# 2VFAT_OH2_OCT1.net
KiCad netlist of a schematic drawn in Altium Designer
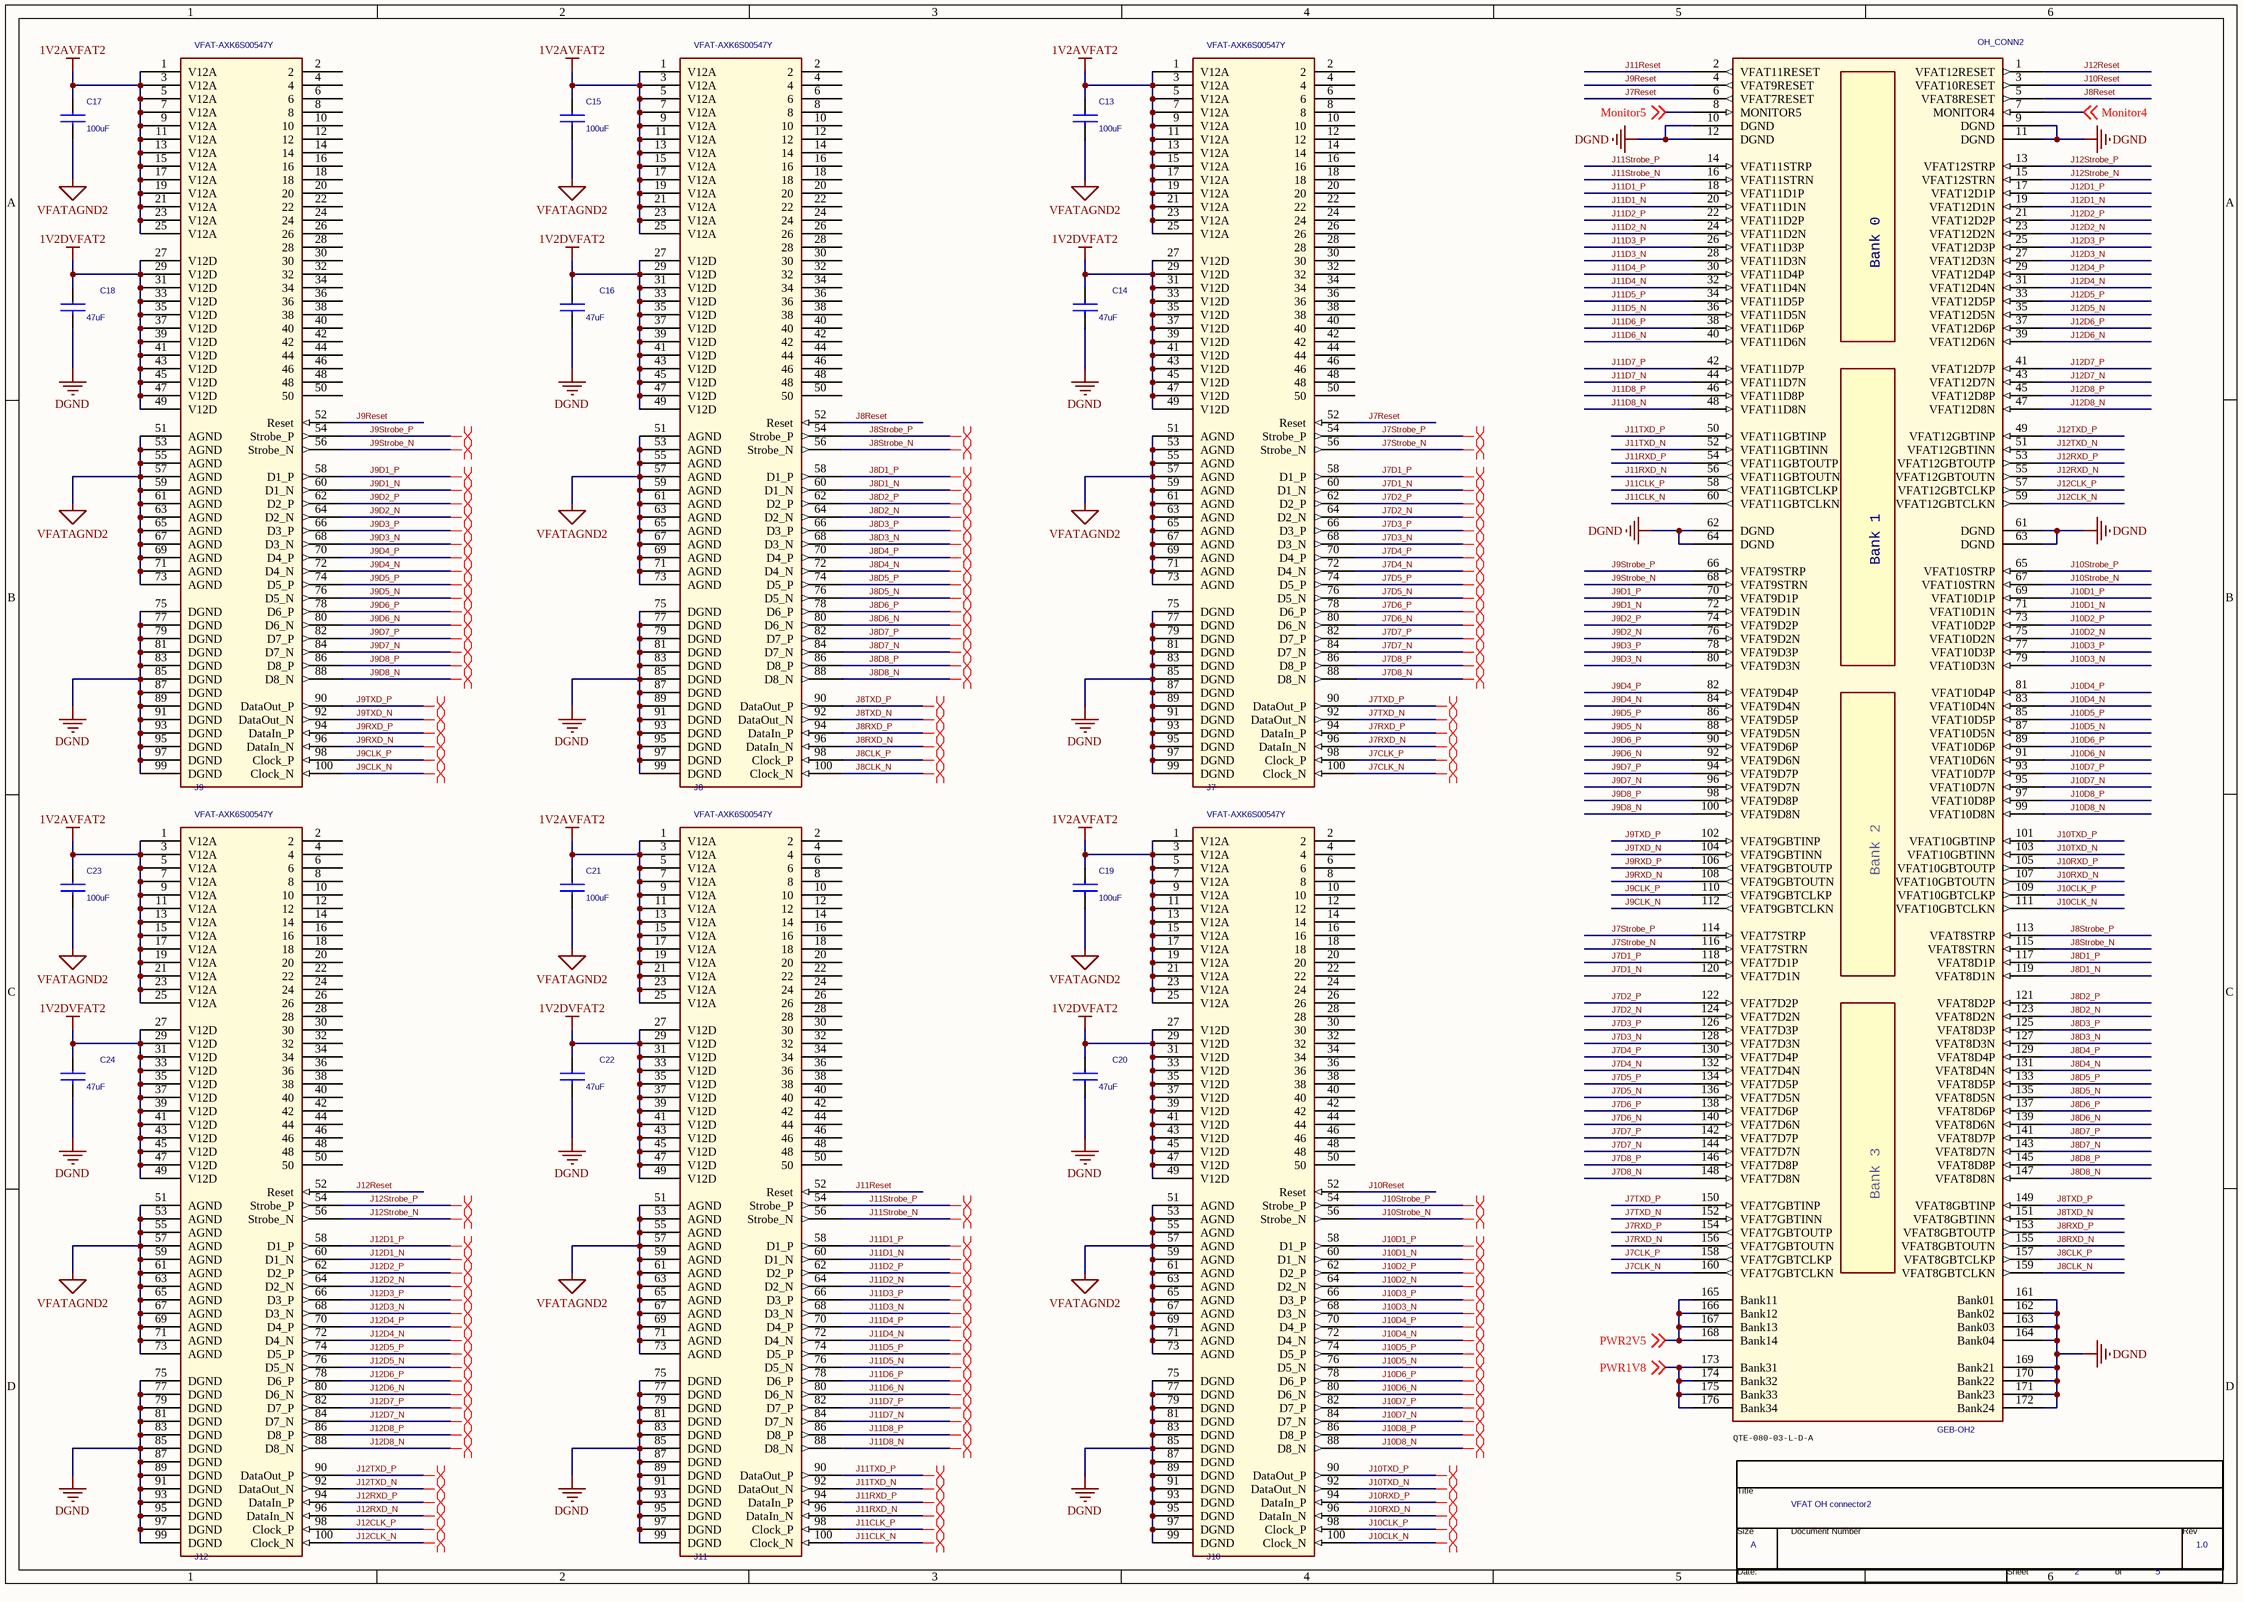
[diagram p0: 2VFAT_OH2_OCT1.SchDoc]

(export (version "E")
  (design (tool "Eeschema 10.0.6"))
  (components
    (comp (ref "*")
      (value "TitleBlock0")
      (fields
        (field (name "PAGE COUNT") "5")
        (field (name "PAGE NUMBER") "2")
        (field (name "PAGE SIZE") "A")
        (field (name "TITLE") "VFAT OH connector2")
        (field (name "REVCODE") "1.0")
      )
      (libsource (lib "*") (part "TitleBlock0"))
    )
    (comp (ref "C13") (value "100uF") (footprint "C1210") (libsource (lib "*") (part "CAP NP")))
    (comp (ref "C14") (value "47uF") (footprint "C1206") (libsource (lib "*") (part "CAP NP")))
    (comp (ref "C15") (value "100uF") (footprint "C1210") (libsource (lib "*") (part "CAP NP")))
    (comp (ref "C16") (value "47uF") (footprint "C1206") (libsource (lib "*") (part "CAP NP")))
    (comp (ref "C17") (value "100uF") (footprint "C1210") (libsource (lib "*") (part "CAP NP")))
    (comp (ref "C18") (value "47uF") (footprint "C1206") (libsource (lib "*") (part "CAP NP")))
    (comp (ref "C19") (value "100uF") (footprint "C1210") (libsource (lib "*") (part "CAP NP")))
    (comp (ref "C20") (value "47uF") (footprint "C1206") (libsource (lib "*") (part "CAP NP")))
    (comp (ref "C21") (value "100uF") (footprint "C1210") (libsource (lib "*") (part "CAP NP")))
    (comp (ref "C22") (value "47uF") (footprint "C1206") (libsource (lib "*") (part "CAP NP")))
    (comp (ref "C23") (value "100uF") (footprint "C1210") (libsource (lib "*") (part "CAP NP")))
    (comp (ref "C24") (value "47uF") (footprint "C1206") (libsource (lib "*") (part "CAP NP")))
    (comp (ref "J7")
      (value "VFAT-AXK6S00547Y")
      (footprint "panasonic100")
      (libsource (lib "*") (part "VFAT-AXK6S00547Y"))
    )
    (comp (ref "J8")
      (value "VFAT-AXK6S00547Y")
      (footprint "panasonic100")
      (libsource (lib "*") (part "VFAT-AXK6S00547Y"))
    )
    (comp (ref "J9")
      (value "VFAT-AXK6S00547Y")
      (footprint "panasonic100")
      (libsource (lib "*") (part "VFAT-AXK6S00547Y"))
    )
    (comp (ref "J10")
      (value "VFAT-AXK6S00547Y")
      (footprint "panasonic100")
      (libsource (lib "*") (part "VFAT-AXK6S00547Y"))
    )
    (comp (ref "J11")
      (value "VFAT-AXK6S00547Y")
      (footprint "panasonic100")
      (libsource (lib "*") (part "VFAT-AXK6S00547Y"))
    )
    (comp (ref "J12")
      (value "VFAT-AXK6S00547Y")
      (footprint "panasonic100")
      (libsource (lib "*") (part "VFAT-AXK6S00547Y"))
    )
    (comp (ref "OH_CONN2") (value "GEB-OH2") (footprint "samtec160") (libsource (lib "*") (part "GEB-OH2")))
  )
  (nets
    (net (code "1") (name "/J7CLK_N") (class "Default")
      (node (ref "J7") (pin "100") (pinfunction "Clock_N_100") (pintype "input"))
      (node (ref "OH_CONN2") (pin "160") (pinfunction "VFAT7GBTCLKN_160") (pintype "output"))
    )
    (net (code "2") (name "/J7CLK_P") (class "Default")
      (node (ref "J7") (pin "98") (pinfunction "Clock_P_98") (pintype "input"))
      (node (ref "OH_CONN2") (pin "158") (pinfunction "VFAT7GBTCLKP_158") (pintype "output"))
    )
    (net (code "3") (name "/J7D1_N") (class "Default")
      (node (ref "J7") (pin "60") (pinfunction "D1_N_60") (pintype "output"))
      (node (ref "OH_CONN2") (pin "120") (pinfunction "VFAT7D1N_120") (pintype "input"))
    )
    (net (code "4") (name "/J7D1_P") (class "Default")
      (node (ref "J7") (pin "58") (pinfunction "D1_P_58") (pintype "output"))
      (node (ref "OH_CONN2") (pin "118") (pinfunction "VFAT7D1P_118") (pintype "input"))
    )
    (net (code "5") (name "/J7D2_N") (class "Default")
      (node (ref "J7") (pin "64") (pinfunction "D2_N_64") (pintype "output"))
      (node (ref "OH_CONN2") (pin "124") (pinfunction "VFAT7D2N_124") (pintype "input"))
    )
    (net (code "6") (name "/J7D2_P") (class "Default")
      (node (ref "J7") (pin "62") (pinfunction "D2_P_62") (pintype "output"))
      (node (ref "OH_CONN2") (pin "122") (pinfunction "VFAT7D2P_122") (pintype "input"))
    )
    (net (code "7") (name "/J7D3_N") (class "Default")
      (node (ref "J7") (pin "68") (pinfunction "D3_N_68") (pintype "output"))
      (node (ref "OH_CONN2") (pin "128") (pinfunction "VFAT7D3N_128") (pintype "input"))
    )
    (net (code "8") (name "/J7D3_P") (class "Default")
      (node (ref "J7") (pin "66") (pinfunction "D3_P_66") (pintype "output"))
      (node (ref "OH_CONN2") (pin "126") (pinfunction "VFAT7D3P_126") (pintype "input"))
    )
    (net (code "9") (name "/J7D4_N") (class "Default")
      (node (ref "J7") (pin "72") (pinfunction "D4_N_72") (pintype "output"))
      (node (ref "OH_CONN2") (pin "132") (pinfunction "VFAT7D4N_132") (pintype "input"))
    )
    (net (code "10") (name "/J7D4_P") (class "Default")
      (node (ref "J7") (pin "70") (pinfunction "D4_P_70") (pintype "output"))
      (node (ref "OH_CONN2") (pin "130") (pinfunction "VFAT7D4P_130") (pintype "input"))
    )
    (net (code "11") (name "/J7D5_N") (class "Default")
      (node (ref "J7") (pin "76") (pinfunction "D5_N_76") (pintype "output"))
      (node (ref "OH_CONN2") (pin "136") (pinfunction "VFAT7D5N_136") (pintype "input"))
    )
    (net (code "12") (name "/J7D5_P") (class "Default")
      (node (ref "J7") (pin "74") (pinfunction "D5_P_74") (pintype "output"))
      (node (ref "OH_CONN2") (pin "134") (pinfunction "VFAT7D5P_134") (pintype "input"))
    )
    (net (code "13") (name "/J7D6_N") (class "Default")
      (node (ref "J7") (pin "80") (pinfunction "D6_N_80") (pintype "output"))
      (node (ref "OH_CONN2") (pin "140") (pinfunction "VFAT7D6N_140") (pintype "input"))
    )
    (net (code "14") (name "/J7D6_P") (class "Default")
      (node (ref "J7") (pin "78") (pinfunction "D6_P_78") (pintype "output"))
      (node (ref "OH_CONN2") (pin "138") (pinfunction "VFAT7D6P_138") (pintype "input"))
    )
    (net (code "15") (name "/J7D7_N") (class "Default")
      (node (ref "J7") (pin "84") (pinfunction "D7_N_84") (pintype "output"))
      (node (ref "OH_CONN2") (pin "144") (pinfunction "VFAT7D7N_144") (pintype "input"))
    )
    (net (code "16") (name "/J7D7_P") (class "Default")
      (node (ref "J7") (pin "82") (pinfunction "D7_P_82") (pintype "output"))
      (node (ref "OH_CONN2") (pin "142") (pinfunction "VFAT7D7P_142") (pintype "input"))
    )
    (net (code "17") (name "/J7D8_N") (class "Default")
      (node (ref "J7") (pin "88") (pinfunction "D8_N_88") (pintype "output"))
      (node (ref "OH_CONN2") (pin "148") (pinfunction "VFAT7D8N_148") (pintype "input"))
    )
    (net (code "18") (name "/J7D8_P") (class "Default")
      (node (ref "J7") (pin "86") (pinfunction "D8_P_86") (pintype "output"))
      (node (ref "OH_CONN2") (pin "146") (pinfunction "VFAT7D8P_146") (pintype "input"))
    )
    (net (code "19") (name "/J7RXD_N") (class "Default")
      (node (ref "J7") (pin "96") (pinfunction "DataIn_N_96") (pintype "input"))
      (node (ref "OH_CONN2") (pin "156") (pinfunction "VFAT7GBTOUTN_156") (pintype "output"))
    )
    (net (code "20") (name "/J7RXD_P") (class "Default")
      (node (ref "J7") (pin "94") (pinfunction "DataIn_P_94") (pintype "input"))
      (node (ref "OH_CONN2") (pin "154") (pinfunction "VFAT7GBTOUTP_154") (pintype "output"))
    )
    (net (code "21") (name "/J7Reset") (class "Default")
      (node (ref "J7") (pin "52") (pinfunction "Reset_52") (pintype "input"))
      (node (ref "OH_CONN2") (pin "6") (pinfunction "VFAT7RESET_6") (pintype "output"))
    )
    (net (code "22") (name "/J7Strobe_N") (class "Default")
      (node (ref "J7") (pin "56") (pinfunction "Strobe_N_56") (pintype "output"))
      (node (ref "OH_CONN2") (pin "116") (pinfunction "VFAT7STRN_116") (pintype "input"))
    )
    (net (code "23") (name "/J7Strobe_P") (class "Default")
      (node (ref "J7") (pin "54") (pinfunction "Strobe_P_54") (pintype "output"))
      (node (ref "OH_CONN2") (pin "114") (pinfunction "VFAT7STRP_114") (pintype "input"))
    )
    (net (code "24") (name "/J7TXD_N") (class "Default")
      (node (ref "J7") (pin "92") (pinfunction "DataOut_N_92") (pintype "output"))
      (node (ref "OH_CONN2") (pin "152") (pinfunction "VFAT7GBTINN_152") (pintype "input"))
    )
    (net (code "25") (name "/J7TXD_P") (class "Default")
      (node (ref "J7") (pin "90") (pinfunction "DataOut_P_90") (pintype "output"))
      (node (ref "OH_CONN2") (pin "150") (pinfunction "VFAT7GBTINP_150") (pintype "input"))
    )
    (net (code "26") (name "/J8CLK_N") (class "Default")
      (node (ref "J8") (pin "100") (pinfunction "Clock_N_100") (pintype "input"))
      (node (ref "OH_CONN2") (pin "159") (pinfunction "VFAT8GBTCLKN_159") (pintype "output"))
    )
    (net (code "27") (name "/J8CLK_P") (class "Default")
      (node (ref "J8") (pin "98") (pinfunction "Clock_P_98") (pintype "input"))
      (node (ref "OH_CONN2") (pin "157") (pinfunction "VFAT8GBTCLKP_157") (pintype "output"))
    )
    (net (code "28") (name "/J8D1_N") (class "Default")
      (node (ref "J8") (pin "60") (pinfunction "D1_N_60") (pintype "output"))
      (node (ref "OH_CONN2") (pin "119") (pinfunction "VFAT8D1N_119") (pintype "input"))
    )
    (net (code "29") (name "/J8D1_P") (class "Default")
      (node (ref "J8") (pin "58") (pinfunction "D1_P_58") (pintype "output"))
      (node (ref "OH_CONN2") (pin "117") (pinfunction "VFAT8D1P_117") (pintype "input"))
    )
    (net (code "30") (name "/J8D2_N") (class "Default")
      (node (ref "J8") (pin "64") (pinfunction "D2_N_64") (pintype "output"))
      (node (ref "OH_CONN2") (pin "123") (pinfunction "VFAT8D2N_123") (pintype "input"))
    )
    (net (code "31") (name "/J8D2_P") (class "Default")
      (node (ref "J8") (pin "62") (pinfunction "D2_P_62") (pintype "output"))
      (node (ref "OH_CONN2") (pin "121") (pinfunction "VFAT8D2P_121") (pintype "input"))
    )
    (net (code "32") (name "/J8D3_N") (class "Default")
      (node (ref "J8") (pin "68") (pinfunction "D3_N_68") (pintype "output"))
      (node (ref "OH_CONN2") (pin "127") (pinfunction "VFAT8D3N_127") (pintype "input"))
    )
    (net (code "33") (name "/J8D3_P") (class "Default")
      (node (ref "J8") (pin "66") (pinfunction "D3_P_66") (pintype "output"))
      (node (ref "OH_CONN2") (pin "125") (pinfunction "VFAT8D3P_125") (pintype "input"))
    )
    (net (code "34") (name "/J8D4_N") (class "Default")
      (node (ref "J8") (pin "72") (pinfunction "D4_N_72") (pintype "output"))
      (node (ref "OH_CONN2") (pin "131") (pinfunction "VFAT8D4N_131") (pintype "input"))
    )
    (net (code "35") (name "/J8D4_P") (class "Default")
      (node (ref "J8") (pin "70") (pinfunction "D4_P_70") (pintype "output"))
      (node (ref "OH_CONN2") (pin "129") (pinfunction "VFAT8D4P_129") (pintype "input"))
    )
    (net (code "36") (name "/J8D5_N") (class "Default")
      (node (ref "J8") (pin "76") (pinfunction "D5_N_76") (pintype "output"))
      (node (ref "OH_CONN2") (pin "135") (pinfunction "VFAT8D5N_135") (pintype "input"))
    )
    (net (code "37") (name "/J8D5_P") (class "Default")
      (node (ref "J8") (pin "74") (pinfunction "D5_P_74") (pintype "output"))
      (node (ref "OH_CONN2") (pin "133") (pinfunction "VFAT8D5P_133") (pintype "input"))
    )
    (net (code "38") (name "/J8D6_N") (class "Default")
      (node (ref "J8") (pin "80") (pinfunction "D6_N_80") (pintype "output"))
      (node (ref "OH_CONN2") (pin "139") (pinfunction "VFAT8D6N_139") (pintype "input"))
    )
    (net (code "39") (name "/J8D6_P") (class "Default")
      (node (ref "J8") (pin "78") (pinfunction "D6_P_78") (pintype "output"))
      (node (ref "OH_CONN2") (pin "137") (pinfunction "VFAT8D6P_137") (pintype "input"))
    )
    (net (code "40") (name "/J8D7_N") (class "Default")
      (node (ref "J8") (pin "84") (pinfunction "D7_N_84") (pintype "output"))
      (node (ref "OH_CONN2") (pin "143") (pinfunction "VFAT8D7N_143") (pintype "input"))
    )
    (net (code "41") (name "/J8D7_P") (class "Default")
      (node (ref "J8") (pin "82") (pinfunction "D7_P_82") (pintype "output"))
      (node (ref "OH_CONN2") (pin "141") (pinfunction "VFAT8D7P_141") (pintype "input"))
    )
    (net (code "42") (name "/J8D8_N") (class "Default")
      (node (ref "J8") (pin "88") (pinfunction "D8_N_88") (pintype "output"))
      (node (ref "OH_CONN2") (pin "147") (pinfunction "VFAT8D8N_147") (pintype "input"))
    )
    (net (code "43") (name "/J8D8_P") (class "Default")
      (node (ref "J8") (pin "86") (pinfunction "D8_P_86") (pintype "output"))
      (node (ref "OH_CONN2") (pin "145") (pinfunction "VFAT8D8P_145") (pintype "input"))
    )
    (net (code "44") (name "/J8RXD_N") (class "Default")
      (node (ref "J8") (pin "96") (pinfunction "DataIn_N_96") (pintype "input"))
      (node (ref "OH_CONN2") (pin "155") (pinfunction "VFAT8GBTOUTN_155") (pintype "output"))
    )
    (net (code "45") (name "/J8RXD_P") (class "Default")
      (node (ref "J8") (pin "94") (pinfunction "DataIn_P_94") (pintype "input"))
      (node (ref "OH_CONN2") (pin "153") (pinfunction "VFAT8GBTOUTP_153") (pintype "output"))
    )
    (net (code "46") (name "/J8Reset") (class "Default")
      (node (ref "J8") (pin "52") (pinfunction "Reset_52") (pintype "input"))
      (node (ref "OH_CONN2") (pin "5") (pinfunction "VFAT8RESET_5") (pintype "output"))
    )
    (net (code "47") (name "/J8Strobe_N") (class "Default")
      (node (ref "J8") (pin "56") (pinfunction "Strobe_N_56") (pintype "output"))
      (node (ref "OH_CONN2") (pin "115") (pinfunction "VFAT8STRN_115") (pintype "input"))
    )
    (net (code "48") (name "/J8Strobe_P") (class "Default")
      (node (ref "J8") (pin "54") (pinfunction "Strobe_P_54") (pintype "output"))
      (node (ref "OH_CONN2") (pin "113") (pinfunction "VFAT8STRP_113") (pintype "input"))
    )
    (net (code "49") (name "/J8TXD_N") (class "Default")
      (node (ref "J8") (pin "92") (pinfunction "DataOut_N_92") (pintype "output"))
      (node (ref "OH_CONN2") (pin "151") (pinfunction "VFAT8GBTINN_151") (pintype "input"))
    )
    (net (code "50") (name "/J8TXD_P") (class "Default")
      (node (ref "J8") (pin "90") (pinfunction "DataOut_P_90") (pintype "output"))
      (node (ref "OH_CONN2") (pin "149") (pinfunction "VFAT8GBTINP_149") (pintype "input"))
    )
    (net (code "51") (name "/J9CLK_N") (class "Default")
      (node (ref "J9") (pin "100") (pinfunction "Clock_N_100") (pintype "input"))
      (node (ref "OH_CONN2") (pin "112") (pinfunction "VFAT9GBTCLKN_112") (pintype "output"))
    )
    (net (code "52") (name "/J9CLK_P") (class "Default")
      (node (ref "J9") (pin "98") (pinfunction "Clock_P_98") (pintype "input"))
      (node (ref "OH_CONN2") (pin "110") (pinfunction "VFAT9GBTCLKP_110") (pintype "output"))
    )
    (net (code "53") (name "/J9D1_N") (class "Default")
      (node (ref "J9") (pin "60") (pinfunction "D1_N_60") (pintype "output"))
      (node (ref "OH_CONN2") (pin "72") (pinfunction "VFAT9D1N_72") (pintype "input"))
    )
    (net (code "54") (name "/J9D1_P") (class "Default")
      (node (ref "J9") (pin "58") (pinfunction "D1_P_58") (pintype "output"))
      (node (ref "OH_CONN2") (pin "70") (pinfunction "VFAT9D1P_70") (pintype "input"))
    )
    (net (code "55") (name "/J9D2_N") (class "Default")
      (node (ref "J9") (pin "64") (pinfunction "D2_N_64") (pintype "output"))
      (node (ref "OH_CONN2") (pin "76") (pinfunction "VFAT9D2N_76") (pintype "input"))
    )
    (net (code "56") (name "/J9D2_P") (class "Default")
      (node (ref "J9") (pin "62") (pinfunction "D2_P_62") (pintype "output"))
      (node (ref "OH_CONN2") (pin "74") (pinfunction "VFAT9D2P_74") (pintype "input"))
    )
    (net (code "57") (name "/J9D3_N") (class "Default")
      (node (ref "J9") (pin "68") (pinfunction "D3_N_68") (pintype "output"))
      (node (ref "OH_CONN2") (pin "80") (pinfunction "VFAT9D3N_80") (pintype "input"))
    )
    (net (code "58") (name "/J9D3_P") (class "Default")
      (node (ref "J9") (pin "66") (pinfunction "D3_P_66") (pintype "output"))
      (node (ref "OH_CONN2") (pin "78") (pinfunction "VFAT9D3P_78") (pintype "input"))
    )
    (net (code "59") (name "/J9D4_N") (class "Default")
      (node (ref "J9") (pin "72") (pinfunction "D4_N_72") (pintype "output"))
      (node (ref "OH_CONN2") (pin "84") (pinfunction "VFAT9D4N_84") (pintype "input"))
    )
    (net (code "60") (name "/J9D4_P") (class "Default")
      (node (ref "J9") (pin "70") (pinfunction "D4_P_70") (pintype "output"))
      (node (ref "OH_CONN2") (pin "82") (pinfunction "VFAT9D4P_82") (pintype "input"))
    )
    (net (code "61") (name "/J9D5_N") (class "Default")
      (node (ref "J9") (pin "76") (pinfunction "D5_N_76") (pintype "output"))
      (node (ref "OH_CONN2") (pin "88") (pinfunction "VFAT9D5N_88") (pintype "input"))
    )
    (net (code "62") (name "/J9D5_P") (class "Default")
      (node (ref "J9") (pin "74") (pinfunction "D5_P_74") (pintype "output"))
      (node (ref "OH_CONN2") (pin "86") (pinfunction "VFAT9D5P_86") (pintype "input"))
    )
    (net (code "63") (name "/J9D6_N") (class "Default")
      (node (ref "J9") (pin "80") (pinfunction "D6_N_80") (pintype "output"))
      (node (ref "OH_CONN2") (pin "92") (pinfunction "VFAT9D6N_92") (pintype "input"))
    )
    (net (code "64") (name "/J9D6_P") (class "Default")
      (node (ref "J9") (pin "78") (pinfunction "D6_P_78") (pintype "output"))
      (node (ref "OH_CONN2") (pin "90") (pinfunction "VFAT9D6P_90") (pintype "input"))
    )
    (net (code "65") (name "/J9D7_N") (class "Default")
      (node (ref "J9") (pin "84") (pinfunction "D7_N_84") (pintype "output"))
      (node (ref "OH_CONN2") (pin "96") (pinfunction "VFAT9D7N_96") (pintype "input"))
    )
    (net (code "66") (name "/J9D7_P") (class "Default")
      (node (ref "J9") (pin "82") (pinfunction "D7_P_82") (pintype "output"))
      (node (ref "OH_CONN2") (pin "94") (pinfunction "VFAT9D7P_94") (pintype "input"))
    )
    (net (code "67") (name "/J9D8_N") (class "Default")
      (node (ref "J9") (pin "88") (pinfunction "D8_N_88") (pintype "output"))
      (node (ref "OH_CONN2") (pin "100") (pinfunction "VFAT9D8N_100") (pintype "input"))
    )
    (net (code "68") (name "/J9D8_P") (class "Default")
      (node (ref "J9") (pin "86") (pinfunction "D8_P_86") (pintype "output"))
      (node (ref "OH_CONN2") (pin "98") (pinfunction "VFAT9D8P_98") (pintype "input"))
    )
    (net (code "69") (name "/J9RXD_N") (class "Default")
      (node (ref "J9") (pin "96") (pinfunction "DataIn_N_96") (pintype "input"))
      (node (ref "OH_CONN2") (pin "108") (pinfunction "VFAT9GBTOUTN_108") (pintype "output"))
    )
    (net (code "70") (name "/J9RXD_P") (class "Default")
      (node (ref "J9") (pin "94") (pinfunction "DataIn_P_94") (pintype "input"))
      (node (ref "OH_CONN2") (pin "106") (pinfunction "VFAT9GBTOUTP_106") (pintype "output"))
    )
    (net (code "71") (name "/J9Reset") (class "Default")
      (node (ref "J9") (pin "52") (pinfunction "Reset_52") (pintype "input"))
      (node (ref "OH_CONN2") (pin "4") (pinfunction "VFAT9RESET_4") (pintype "output"))
    )
    (net (code "72") (name "/J9Strobe_N") (class "Default")
      (node (ref "J9") (pin "56") (pinfunction "Strobe_N_56") (pintype "output"))
      (node (ref "OH_CONN2") (pin "68") (pinfunction "VFAT9STRN_68") (pintype "input"))
    )
    (net (code "73") (name "/J9Strobe_P") (class "Default")
      (node (ref "J9") (pin "54") (pinfunction "Strobe_P_54") (pintype "output"))
      (node (ref "OH_CONN2") (pin "66") (pinfunction "VFAT9STRP_66") (pintype "input"))
    )
    (net (code "74") (name "/J9TXD_N") (class "Default")
      (node (ref "J9") (pin "92") (pinfunction "DataOut_N_92") (pintype "output"))
      (node (ref "OH_CONN2") (pin "104") (pinfunction "VFAT9GBTINN_104") (pintype "input"))
    )
    (net (code "75") (name "/J9TXD_P") (class "Default")
      (node (ref "J9") (pin "90") (pinfunction "DataOut_P_90") (pintype "output"))
      (node (ref "OH_CONN2") (pin "102") (pinfunction "VFAT9GBTINP_102") (pintype "input"))
    )
    (net (code "76") (name "/J10CLK_N") (class "Default")
      (node (ref "J10") (pin "100") (pinfunction "Clock_N_100") (pintype "input"))
      (node (ref "OH_CONN2") (pin "111") (pinfunction "VFAT10GBTCLKN_111") (pintype "output"))
    )
    (net (code "77") (name "/J10CLK_P") (class "Default")
      (node (ref "J10") (pin "98") (pinfunction "Clock_P_98") (pintype "input"))
      (node (ref "OH_CONN2") (pin "109") (pinfunction "VFAT10GBTCLKP_109") (pintype "output"))
    )
    (net (code "78") (name "/J10D1_N") (class "Default")
      (node (ref "J10") (pin "60") (pinfunction "D1_N_60") (pintype "output"))
      (node (ref "OH_CONN2") (pin "71") (pinfunction "VFAT10D1N_71") (pintype "input"))
    )
    (net (code "79") (name "/J10D1_P") (class "Default")
      (node (ref "J10") (pin "58") (pinfunction "D1_P_58") (pintype "output"))
      (node (ref "OH_CONN2") (pin "69") (pinfunction "VFAT10D1P_69") (pintype "input"))
    )
    (net (code "80") (name "/J10D2_N") (class "Default")
      (node (ref "J10") (pin "64") (pinfunction "D2_N_64") (pintype "output"))
      (node (ref "OH_CONN2") (pin "75") (pinfunction "VFAT10D2N_75") (pintype "input"))
    )
    (net (code "81") (name "/J10D2_P") (class "Default")
      (node (ref "J10") (pin "62") (pinfunction "D2_P_62") (pintype "output"))
      (node (ref "OH_CONN2") (pin "73") (pinfunction "VFAT10D2P_73") (pintype "input"))
    )
    (net (code "82") (name "/J10D3_N") (class "Default")
      (node (ref "J10") (pin "68") (pinfunction "D3_N_68") (pintype "output"))
      (node (ref "OH_CONN2") (pin "79") (pinfunction "VFAT10D3N_79") (pintype "input"))
    )
    (net (code "83") (name "/J10D3_P") (class "Default")
      (node (ref "J10") (pin "66") (pinfunction "D3_P_66") (pintype "output"))
      (node (ref "OH_CONN2") (pin "77") (pinfunction "VFAT10D3P_77") (pintype "input"))
    )
    (net (code "84") (name "/J10D4_N") (class "Default")
      (node (ref "J10") (pin "72") (pinfunction "D4_N_72") (pintype "output"))
      (node (ref "OH_CONN2") (pin "83") (pinfunction "VFAT10D4N_83") (pintype "input"))
    )
    (net (code "85") (name "/J10D4_P") (class "Default")
      (node (ref "J10") (pin "70") (pinfunction "D4_P_70") (pintype "output"))
      (node (ref "OH_CONN2") (pin "81") (pinfunction "VFAT10D4P_81") (pintype "input"))
    )
    (net (code "86") (name "/J10D5_N") (class "Default")
      (node (ref "J10") (pin "76") (pinfunction "D5_N_76") (pintype "output"))
      (node (ref "OH_CONN2") (pin "87") (pinfunction "VFAT10D5N_87") (pintype "input"))
    )
    (net (code "87") (name "/J10D5_P") (class "Default")
      (node (ref "J10") (pin "74") (pinfunction "D5_P_74") (pintype "output"))
      (node (ref "OH_CONN2") (pin "85") (pinfunction "VFAT10D5P_85") (pintype "input"))
    )
    (net (code "88") (name "/J10D6_N") (class "Default")
      (node (ref "J10") (pin "80") (pinfunction "D6_N_80") (pintype "output"))
      (node (ref "OH_CONN2") (pin "91") (pinfunction "VFAT10D6N_91") (pintype "input"))
    )
    (net (code "89") (name "/J10D6_P") (class "Default")
      (node (ref "J10") (pin "78") (pinfunction "D6_P_78") (pintype "output"))
      (node (ref "OH_CONN2") (pin "89") (pinfunction "VFAT10D6P_89") (pintype "input"))
    )
    (net (code "90") (name "/J10D7_N") (class "Default")
      (node (ref "J10") (pin "84") (pinfunction "D7_N_84") (pintype "output"))
      (node (ref "OH_CONN2") (pin "95") (pinfunction "VFAT10D7N_95") (pintype "input"))
    )
    (net (code "91") (name "/J10D7_P") (class "Default")
      (node (ref "J10") (pin "82") (pinfunction "D7_P_82") (pintype "output"))
      (node (ref "OH_CONN2") (pin "93") (pinfunction "VFAT10D7P_93") (pintype "input"))
    )
    (net (code "92") (name "/J10D8_N") (class "Default")
      (node (ref "J10") (pin "88") (pinfunction "D8_N_88") (pintype "output"))
      (node (ref "OH_CONN2") (pin "99") (pinfunction "VFAT10D8N_99") (pintype "input"))
    )
    (net (code "93") (name "/J10D8_P") (class "Default")
      (node (ref "J10") (pin "86") (pinfunction "D8_P_86") (pintype "output"))
      (node (ref "OH_CONN2") (pin "97") (pinfunction "VFAT10D8P_97") (pintype "input"))
    )
    (net (code "94") (name "/J10RXD_N") (class "Default")
      (node (ref "J10") (pin "96") (pinfunction "DataIn_N_96") (pintype "input"))
      (node (ref "OH_CONN2") (pin "107") (pinfunction "VFAT10GBTOUTN_107") (pintype "output"))
    )
    (net (code "95") (name "/J10RXD_P") (class "Default")
      (node (ref "J10") (pin "94") (pinfunction "DataIn_P_94") (pintype "input"))
      (node (ref "OH_CONN2") (pin "105") (pinfunction "VFAT10GBTOUTP_105") (pintype "output"))
    )
    (net (code "96") (name "/J10Reset") (class "Default")
      (node (ref "J10") (pin "52") (pinfunction "Reset_52") (pintype "input"))
      (node (ref "OH_CONN2") (pin "3") (pinfunction "VFAT10RESET_3") (pintype "output"))
    )
    (net (code "97") (name "/J10Strobe_N") (class "Default")
      (node (ref "J10") (pin "56") (pinfunction "Strobe_N_56") (pintype "output"))
      (node (ref "OH_CONN2") (pin "67") (pinfunction "VFAT10STRN_67") (pintype "input"))
    )
    (net (code "98") (name "/J10Strobe_P") (class "Default")
      (node (ref "J10") (pin "54") (pinfunction "Strobe_P_54") (pintype "output"))
      (node (ref "OH_CONN2") (pin "65") (pinfunction "VFAT10STRP_65") (pintype "input"))
    )
    (net (code "99") (name "/J10TXD_N") (class "Default")
      (node (ref "J10") (pin "92") (pinfunction "DataOut_N_92") (pintype "output"))
      (node (ref "OH_CONN2") (pin "103") (pinfunction "VFAT10GBTINN_103") (pintype "input"))
    )
    (net (code "100") (name "/J10TXD_P") (class "Default")
      (node (ref "J10") (pin "90") (pinfunction "DataOut_P_90") (pintype "output"))
      (node (ref "OH_CONN2") (pin "101") (pinfunction "VFAT10GBTINP_101") (pintype "input"))
    )
    (net (code "101") (name "/J11CLK_N") (class "Default")
      (node (ref "J11") (pin "100") (pinfunction "Clock_N_100") (pintype "input"))
      (node (ref "OH_CONN2") (pin "60") (pinfunction "VFAT11GBTCLKN_60") (pintype "output"))
    )
    (net (code "102") (name "/J11CLK_P") (class "Default")
      (node (ref "J11") (pin "98") (pinfunction "Clock_P_98") (pintype "input"))
      (node (ref "OH_CONN2") (pin "58") (pinfunction "VFAT11GBTCLKP_58") (pintype "output"))
    )
    (net (code "103") (name "/J11D1_N") (class "Default")
      (node (ref "J11") (pin "60") (pinfunction "D1_N_60") (pintype "output"))
      (node (ref "OH_CONN2") (pin "20") (pinfunction "VFAT11D1N_20") (pintype "input"))
    )
    (net (code "104") (name "/J11D1_P") (class "Default")
      (node (ref "J11") (pin "58") (pinfunction "D1_P_58") (pintype "output"))
      (node (ref "OH_CONN2") (pin "18") (pinfunction "VFAT11D1P_18") (pintype "input"))
    )
    (net (code "105") (name "/J11D2_N") (class "Default")
      (node (ref "J11") (pin "64") (pinfunction "D2_N_64") (pintype "output"))
      (node (ref "OH_CONN2") (pin "24") (pinfunction "VFAT11D2N_24") (pintype "input"))
    )
    (net (code "106") (name "/J11D2_P") (class "Default")
      (node (ref "J11") (pin "62") (pinfunction "D2_P_62") (pintype "output"))
      (node (ref "OH_CONN2") (pin "22") (pinfunction "VFAT11D2P_22") (pintype "input"))
    )
    (net (code "107") (name "/J11D3_N") (class "Default")
      (node (ref "J11") (pin "68") (pinfunction "D3_N_68") (pintype "output"))
      (node (ref "OH_CONN2") (pin "28") (pinfunction "VFAT11D3N_28") (pintype "input"))
    )
    (net (code "108") (name "/J11D3_P") (class "Default")
      (node (ref "J11") (pin "66") (pinfunction "D3_P_66") (pintype "output"))
      (node (ref "OH_CONN2") (pin "26") (pinfunction "VFAT11D3P_26") (pintype "input"))
    )
    (net (code "109") (name "/J11D4_N") (class "Default")
      (node (ref "J11") (pin "72") (pinfunction "D4_N_72") (pintype "output"))
      (node (ref "OH_CONN2") (pin "32") (pinfunction "VFAT11D4N_32") (pintype "input"))
    )
    (net (code "110") (name "/J11D4_P") (class "Default")
      (node (ref "J11") (pin "70") (pinfunction "D4_P_70") (pintype "output"))
      (node (ref "OH_CONN2") (pin "30") (pinfunction "VFAT11D4P_30") (pintype "input"))
    )
    (net (code "111") (name "/J11D5_N") (class "Default")
      (node (ref "J11") (pin "76") (pinfunction "D5_N_76") (pintype "output"))
      (node (ref "OH_CONN2") (pin "36") (pinfunction "VFAT11D5N_36") (pintype "input"))
    )
    (net (code "112") (name "/J11D5_P") (class "Default")
      (node (ref "J11") (pin "74") (pinfunction "D5_P_74") (pintype "output"))
      (node (ref "OH_CONN2") (pin "34") (pinfunction "VFAT11D5P_34") (pintype "input"))
    )
    (net (code "113") (name "/J11D6_N") (class "Default")
      (node (ref "J11") (pin "80") (pinfunction "D6_N_80") (pintype "output"))
      (node (ref "OH_CONN2") (pin "40") (pinfunction "VFAT11D6N_40") (pintype "input"))
    )
    (net (code "114") (name "/J11D6_P") (class "Default")
      (node (ref "J11") (pin "78") (pinfunction "D6_P_78") (pintype "output"))
      (node (ref "OH_CONN2") (pin "38") (pinfunction "VFAT11D6P_38") (pintype "input"))
    )
    (net (code "115") (name "/J11D7_N") (class "Default")
      (node (ref "J11") (pin "84") (pinfunction "D7_N_84") (pintype "output"))
      (node (ref "OH_CONN2") (pin "44") (pinfunction "VFAT11D7N_44") (pintype "input"))
    )
    (net (code "116") (name "/J11D7_P") (class "Default")
      (node (ref "J11") (pin "82") (pinfunction "D7_P_82") (pintype "output"))
      (node (ref "OH_CONN2") (pin "42") (pinfunction "VFAT11D7P_42") (pintype "input"))
    )
    (net (code "117") (name "/J11D8_N") (class "Default")
      (node (ref "J11") (pin "88") (pinfunction "D8_N_88") (pintype "output"))
      (node (ref "OH_CONN2") (pin "48") (pinfunction "VFAT11D8N_48") (pintype "input"))
    )
    (net (code "118") (name "/J11D8_P") (class "Default")
      (node (ref "J11") (pin "86") (pinfunction "D8_P_86") (pintype "output"))
      (node (ref "OH_CONN2") (pin "46") (pinfunction "VFAT11D8P_46") (pintype "input"))
    )
    (net (code "119") (name "/J11RXD_N") (class "Default")
      (node (ref "J11") (pin "96") (pinfunction "DataIn_N_96") (pintype "input"))
      (node (ref "OH_CONN2") (pin "56") (pinfunction "VFAT11GBTOUTN_56") (pintype "output"))
    )
    (net (code "120") (name "/J11RXD_P") (class "Default")
      (node (ref "J11") (pin "94") (pinfunction "DataIn_P_94") (pintype "input"))
      (node (ref "OH_CONN2") (pin "54") (pinfunction "VFAT11GBTOUTP_54") (pintype "output"))
    )
    (net (code "121") (name "/J11Reset") (class "Default")
      (node (ref "J11") (pin "52") (pinfunction "Reset_52") (pintype "input"))
      (node (ref "OH_CONN2") (pin "2") (pinfunction "VFAT11RESET_2") (pintype "output"))
    )
    (net (code "122") (name "/J11Strobe_N") (class "Default")
      (node (ref "J11") (pin "56") (pinfunction "Strobe_N_56") (pintype "output"))
      (node (ref "OH_CONN2") (pin "16") (pinfunction "VFAT11STRN_16") (pintype "input"))
    )
    (net (code "123") (name "/J11Strobe_P") (class "Default")
      (node (ref "J11") (pin "54") (pinfunction "Strobe_P_54") (pintype "output"))
      (node (ref "OH_CONN2") (pin "14") (pinfunction "VFAT11STRP_14") (pintype "input"))
    )
    (net (code "124") (name "/J11TXD_N") (class "Default")
      (node (ref "J11") (pin "92") (pinfunction "DataOut_N_92") (pintype "output"))
      (node (ref "OH_CONN2") (pin "52") (pinfunction "VFAT11GBTINN_52") (pintype "input"))
    )
    (net (code "125") (name "/J11TXD_P") (class "Default")
      (node (ref "J11") (pin "90") (pinfunction "DataOut_P_90") (pintype "output"))
      (node (ref "OH_CONN2") (pin "50") (pinfunction "VFAT11GBTINP_50") (pintype "input"))
    )
    (net (code "126") (name "/J12CLK_N") (class "Default")
      (node (ref "J12") (pin "100") (pinfunction "Clock_N_100") (pintype "input"))
      (node (ref "OH_CONN2") (pin "59") (pinfunction "VFAT12GBTCLKN_59") (pintype "output"))
    )
    (net (code "127") (name "/J12CLK_P") (class "Default")
      (node (ref "J12") (pin "98") (pinfunction "Clock_P_98") (pintype "input"))
      (node (ref "OH_CONN2") (pin "57") (pinfunction "VFAT12GBTCLKP_57") (pintype "output"))
    )
    (net (code "128") (name "/J12D1_N") (class "Default")
      (node (ref "J12") (pin "60") (pinfunction "D1_N_60") (pintype "output"))
      (node (ref "OH_CONN2") (pin "19") (pinfunction "VFAT12D1N_19") (pintype "input"))
    )
    (net (code "129") (name "/J12D1_P") (class "Default")
      (node (ref "J12") (pin "58") (pinfunction "D1_P_58") (pintype "output"))
      (node (ref "OH_CONN2") (pin "17") (pinfunction "VFAT12D1P_17") (pintype "input"))
    )
    (net (code "130") (name "/J12D2_N") (class "Default")
      (node (ref "J12") (pin "64") (pinfunction "D2_N_64") (pintype "output"))
      (node (ref "OH_CONN2") (pin "23") (pinfunction "VFAT12D2N_23") (pintype "input"))
    )
    (net (code "131") (name "/J12D2_P") (class "Default")
      (node (ref "J12") (pin "62") (pinfunction "D2_P_62") (pintype "output"))
      (node (ref "OH_CONN2") (pin "21") (pinfunction "VFAT12D2P_21") (pintype "input"))
    )
    (net (code "132") (name "/J12D3_N") (class "Default")
      (node (ref "J12") (pin "68") (pinfunction "D3_N_68") (pintype "output"))
      (node (ref "OH_CONN2") (pin "27") (pinfunction "VFAT12D3N_27") (pintype "input"))
    )
    (net (code "133") (name "/J12D3_P") (class "Default")
      (node (ref "J12") (pin "66") (pinfunction "D3_P_66") (pintype "output"))
      (node (ref "OH_CONN2") (pin "25") (pinfunction "VFAT12D3P_25") (pintype "input"))
    )
    (net (code "134") (name "/J12D4_N") (class "Default")
      (node (ref "J12") (pin "72") (pinfunction "D4_N_72") (pintype "output"))
      (node (ref "OH_CONN2") (pin "31") (pinfunction "VFAT12D4N_31") (pintype "input"))
    )
    (net (code "135") (name "/J12D4_P") (class "Default")
      (node (ref "J12") (pin "70") (pinfunction "D4_P_70") (pintype "output"))
      (node (ref "OH_CONN2") (pin "29") (pinfunction "VFAT12D4P_29") (pintype "input"))
    )
    (net (code "136") (name "/J12D5_N") (class "Default")
      (node (ref "J12") (pin "76") (pinfunction "D5_N_76") (pintype "output"))
      (node (ref "OH_CONN2") (pin "35") (pinfunction "VFAT12D5N_35") (pintype "input"))
    )
    (net (code "137") (name "/J12D5_P") (class "Default")
      (node (ref "J12") (pin "74") (pinfunction "D5_P_74") (pintype "output"))
      (node (ref "OH_CONN2") (pin "33") (pinfunction "VFAT12D5P_33") (pintype "input"))
    )
    (net (code "138") (name "/J12D6_N") (class "Default")
      (node (ref "J12") (pin "80") (pinfunction "D6_N_80") (pintype "output"))
      (node (ref "OH_CONN2") (pin "39") (pinfunction "VFAT12D6N_39") (pintype "input"))
    )
    (net (code "139") (name "/J12D6_P") (class "Default")
      (node (ref "J12") (pin "78") (pinfunction "D6_P_78") (pintype "output"))
      (node (ref "OH_CONN2") (pin "37") (pinfunction "VFAT12D6P_37") (pintype "input"))
    )
    (net (code "140") (name "/J12D7_N") (class "Default")
      (node (ref "J12") (pin "84") (pinfunction "D7_N_84") (pintype "output"))
      (node (ref "OH_CONN2") (pin "43") (pinfunction "VFAT12D7N_43") (pintype "input"))
    )
    (net (code "141") (name "/J12D7_P") (class "Default")
      (node (ref "J12") (pin "82") (pinfunction "D7_P_82") (pintype "output"))
      (node (ref "OH_CONN2") (pin "41") (pinfunction "VFAT12D7P_41") (pintype "input"))
    )
    (net (code "142") (name "/J12D8_N") (class "Default")
      (node (ref "J12") (pin "88") (pinfunction "D8_N_88") (pintype "output"))
      (node (ref "OH_CONN2") (pin "47") (pinfunction "VFAT12D8N_47") (pintype "input"))
    )
    (net (code "143") (name "/J12D8_P") (class "Default")
      (node (ref "J12") (pin "86") (pinfunction "D8_P_86") (pintype "output"))
      (node (ref "OH_CONN2") (pin "45") (pinfunction "VFAT12D8P_45") (pintype "input"))
    )
    (net (code "144") (name "/J12RXD_N") (class "Default")
      (node (ref "J12") (pin "96") (pinfunction "DataIn_N_96") (pintype "input"))
      (node (ref "OH_CONN2") (pin "55") (pinfunction "VFAT12GBTOUTN_55") (pintype "output"))
    )
    (net (code "145") (name "/J12RXD_P") (class "Default")
      (node (ref "J12") (pin "94") (pinfunction "DataIn_P_94") (pintype "input"))
      (node (ref "OH_CONN2") (pin "53") (pinfunction "VFAT12GBTOUTP_53") (pintype "output"))
    )
    (net (code "146") (name "/J12Reset") (class "Default")
      (node (ref "J12") (pin "52") (pinfunction "Reset_52") (pintype "input"))
      (node (ref "OH_CONN2") (pin "1") (pinfunction "VFAT12RESET_1") (pintype "output"))
    )
    (net (code "147") (name "/J12Strobe_N") (class "Default")
      (node (ref "J12") (pin "56") (pinfunction "Strobe_N_56") (pintype "output"))
      (node (ref "OH_CONN2") (pin "15") (pinfunction "VFAT12STRN_15") (pintype "input"))
    )
    (net (code "148") (name "/J12Strobe_P") (class "Default")
      (node (ref "J12") (pin "54") (pinfunction "Strobe_P_54") (pintype "output"))
      (node (ref "OH_CONN2") (pin "13") (pinfunction "VFAT12STRP_13") (pintype "input"))
    )
    (net (code "149") (name "/J12TXD_N") (class "Default")
      (node (ref "J12") (pin "92") (pinfunction "DataOut_N_92") (pintype "output"))
      (node (ref "OH_CONN2") (pin "51") (pinfunction "VFAT12GBTINN_51") (pintype "input"))
    )
    (net (code "150") (name "/J12TXD_P") (class "Default")
      (node (ref "J12") (pin "90") (pinfunction "DataOut_P_90") (pintype "output"))
      (node (ref "OH_CONN2") (pin "49") (pinfunction "VFAT12GBTINP_49") (pintype "input"))
    )
    (net (code "151") (name "1V2AVFAT2") (class "Default")
      (node (ref "C13") (pin "1") (pinfunction "1_1") (pintype "passive"))
      (node (ref "C15") (pin "1") (pinfunction "1_1") (pintype "passive"))
      (node (ref "C17") (pin "1") (pinfunction "1_1") (pintype "passive"))
      (node (ref "C19") (pin "1") (pinfunction "1_1") (pintype "passive"))
      (node (ref "C21") (pin "1") (pinfunction "1_1") (pintype "passive"))
      (node (ref "C23") (pin "1") (pinfunction "1_1") (pintype "passive"))
      (node (ref "J10") (pin "1") (pinfunction "V12A_1") (pintype "power_in"))
      (node (ref "J10") (pin "11") (pinfunction "V12A_11") (pintype "power_in"))
      (node (ref "J10") (pin "13") (pinfunction "V12A_13") (pintype "power_in"))
      (node (ref "J10") (pin "15") (pinfunction "V12A_15") (pintype "power_in"))
      (node (ref "J10") (pin "17") (pinfunction "V12A_17") (pintype "power_in"))
      (node (ref "J10") (pin "19") (pinfunction "V12A_19") (pintype "power_in"))
      (node (ref "J10") (pin "21") (pinfunction "V12A_21") (pintype "power_in"))
      (node (ref "J10") (pin "23") (pinfunction "V12A_23") (pintype "power_in"))
      (node (ref "J10") (pin "25") (pinfunction "V12A_25") (pintype "power_in"))
      (node (ref "J10") (pin "3") (pinfunction "V12A_3") (pintype "power_in"))
      (node (ref "J10") (pin "5") (pinfunction "V12A_5") (pintype "power_in"))
      (node (ref "J10") (pin "7") (pinfunction "V12A_7") (pintype "power_in"))
      (node (ref "J10") (pin "9") (pinfunction "V12A_9") (pintype "power_in"))
      (node (ref "J11") (pin "1") (pinfunction "V12A_1") (pintype "power_in"))
      (node (ref "J11") (pin "11") (pinfunction "V12A_11") (pintype "power_in"))
      (node (ref "J11") (pin "13") (pinfunction "V12A_13") (pintype "power_in"))
      (node (ref "J11") (pin "15") (pinfunction "V12A_15") (pintype "power_in"))
      (node (ref "J11") (pin "17") (pinfunction "V12A_17") (pintype "power_in"))
      (node (ref "J11") (pin "19") (pinfunction "V12A_19") (pintype "power_in"))
      (node (ref "J11") (pin "21") (pinfunction "V12A_21") (pintype "power_in"))
      (node (ref "J11") (pin "23") (pinfunction "V12A_23") (pintype "power_in"))
      (node (ref "J11") (pin "25") (pinfunction "V12A_25") (pintype "power_in"))
      (node (ref "J11") (pin "3") (pinfunction "V12A_3") (pintype "power_in"))
      (node (ref "J11") (pin "5") (pinfunction "V12A_5") (pintype "power_in"))
      (node (ref "J11") (pin "7") (pinfunction "V12A_7") (pintype "power_in"))
      (node (ref "J11") (pin "9") (pinfunction "V12A_9") (pintype "power_in"))
      (node (ref "J12") (pin "1") (pinfunction "V12A_1") (pintype "power_in"))
      (node (ref "J12") (pin "11") (pinfunction "V12A_11") (pintype "power_in"))
      (node (ref "J12") (pin "13") (pinfunction "V12A_13") (pintype "power_in"))
      (node (ref "J12") (pin "15") (pinfunction "V12A_15") (pintype "power_in"))
      (node (ref "J12") (pin "17") (pinfunction "V12A_17") (pintype "power_in"))
      (node (ref "J12") (pin "19") (pinfunction "V12A_19") (pintype "power_in"))
      (node (ref "J12") (pin "21") (pinfunction "V12A_21") (pintype "power_in"))
      (node (ref "J12") (pin "23") (pinfunction "V12A_23") (pintype "power_in"))
      (node (ref "J12") (pin "25") (pinfunction "V12A_25") (pintype "power_in"))
      (node (ref "J12") (pin "3") (pinfunction "V12A_3") (pintype "power_in"))
      (node (ref "J12") (pin "5") (pinfunction "V12A_5") (pintype "power_in"))
      (node (ref "J12") (pin "7") (pinfunction "V12A_7") (pintype "power_in"))
      (node (ref "J12") (pin "9") (pinfunction "V12A_9") (pintype "power_in"))
      (node (ref "J7") (pin "1") (pinfunction "V12A_1") (pintype "power_in"))
      (node (ref "J7") (pin "11") (pinfunction "V12A_11") (pintype "power_in"))
      (node (ref "J7") (pin "13") (pinfunction "V12A_13") (pintype "power_in"))
      (node (ref "J7") (pin "15") (pinfunction "V12A_15") (pintype "power_in"))
      (node (ref "J7") (pin "17") (pinfunction "V12A_17") (pintype "power_in"))
      (node (ref "J7") (pin "19") (pinfunction "V12A_19") (pintype "power_in"))
      (node (ref "J7") (pin "21") (pinfunction "V12A_21") (pintype "power_in"))
      (node (ref "J7") (pin "23") (pinfunction "V12A_23") (pintype "power_in"))
      (node (ref "J7") (pin "25") (pinfunction "V12A_25") (pintype "power_in"))
      (node (ref "J7") (pin "3") (pinfunction "V12A_3") (pintype "power_in"))
      (node (ref "J7") (pin "5") (pinfunction "V12A_5") (pintype "power_in"))
      (node (ref "J7") (pin "7") (pinfunction "V12A_7") (pintype "power_in"))
      (node (ref "J7") (pin "9") (pinfunction "V12A_9") (pintype "power_in"))
      (node (ref "J8") (pin "1") (pinfunction "V12A_1") (pintype "power_in"))
      (node (ref "J8") (pin "11") (pinfunction "V12A_11") (pintype "power_in"))
      (node (ref "J8") (pin "13") (pinfunction "V12A_13") (pintype "power_in"))
      (node (ref "J8") (pin "15") (pinfunction "V12A_15") (pintype "power_in"))
      (node (ref "J8") (pin "17") (pinfunction "V12A_17") (pintype "power_in"))
      (node (ref "J8") (pin "19") (pinfunction "V12A_19") (pintype "power_in"))
      (node (ref "J8") (pin "21") (pinfunction "V12A_21") (pintype "power_in"))
      (node (ref "J8") (pin "23") (pinfunction "V12A_23") (pintype "power_in"))
      (node (ref "J8") (pin "25") (pinfunction "V12A_25") (pintype "power_in"))
      (node (ref "J8") (pin "3") (pinfunction "V12A_3") (pintype "power_in"))
      (node (ref "J8") (pin "5") (pinfunction "V12A_5") (pintype "power_in"))
      (node (ref "J8") (pin "7") (pinfunction "V12A_7") (pintype "power_in"))
      (node (ref "J8") (pin "9") (pinfunction "V12A_9") (pintype "power_in"))
      (node (ref "J9") (pin "1") (pinfunction "V12A_1") (pintype "power_in"))
      (node (ref "J9") (pin "11") (pinfunction "V12A_11") (pintype "power_in"))
      (node (ref "J9") (pin "13") (pinfunction "V12A_13") (pintype "power_in"))
      (node (ref "J9") (pin "15") (pinfunction "V12A_15") (pintype "power_in"))
      (node (ref "J9") (pin "17") (pinfunction "V12A_17") (pintype "power_in"))
      (node (ref "J9") (pin "19") (pinfunction "V12A_19") (pintype "power_in"))
      (node (ref "J9") (pin "21") (pinfunction "V12A_21") (pintype "power_in"))
      (node (ref "J9") (pin "23") (pinfunction "V12A_23") (pintype "power_in"))
      (node (ref "J9") (pin "25") (pinfunction "V12A_25") (pintype "power_in"))
      (node (ref "J9") (pin "3") (pinfunction "V12A_3") (pintype "power_in"))
      (node (ref "J9") (pin "5") (pinfunction "V12A_5") (pintype "power_in"))
      (node (ref "J9") (pin "7") (pinfunction "V12A_7") (pintype "power_in"))
      (node (ref "J9") (pin "9") (pinfunction "V12A_9") (pintype "power_in"))
    )
    (net (code "152") (name "1V2DVFAT2") (class "Default")
      (node (ref "C14") (pin "1") (pinfunction "1_1") (pintype "passive"))
      (node (ref "C16") (pin "1") (pinfunction "1_1") (pintype "passive"))
      (node (ref "C18") (pin "1") (pinfunction "1_1") (pintype "passive"))
      (node (ref "C20") (pin "1") (pinfunction "1_1") (pintype "passive"))
      (node (ref "C22") (pin "1") (pinfunction "1_1") (pintype "passive"))
      (node (ref "C24") (pin "1") (pinfunction "1_1") (pintype "passive"))
      (node (ref "J10") (pin "27") (pinfunction "V12D_27") (pintype "power_in"))
      (node (ref "J10") (pin "29") (pinfunction "V12D_29") (pintype "power_in"))
      (node (ref "J10") (pin "31") (pinfunction "V12D_31") (pintype "power_in"))
      (node (ref "J10") (pin "33") (pinfunction "V12D_33") (pintype "power_in"))
      (node (ref "J10") (pin "35") (pinfunction "V12D_35") (pintype "power_in"))
      (node (ref "J10") (pin "37") (pinfunction "V12D_37") (pintype "power_in"))
      (node (ref "J10") (pin "39") (pinfunction "V12D_39") (pintype "power_in"))
      (node (ref "J10") (pin "41") (pinfunction "V12D_41") (pintype "power_in"))
      (node (ref "J10") (pin "43") (pinfunction "V12D_43") (pintype "power_in"))
      (node (ref "J10") (pin "45") (pinfunction "V12D_45") (pintype "power_in"))
      (node (ref "J10") (pin "47") (pinfunction "V12D_47") (pintype "power_in"))
      (node (ref "J10") (pin "49") (pinfunction "V12D_49") (pintype "power_in"))
      (node (ref "J11") (pin "27") (pinfunction "V12D_27") (pintype "power_in"))
      (node (ref "J11") (pin "29") (pinfunction "V12D_29") (pintype "power_in"))
      (node (ref "J11") (pin "31") (pinfunction "V12D_31") (pintype "power_in"))
      (node (ref "J11") (pin "33") (pinfunction "V12D_33") (pintype "power_in"))
      (node (ref "J11") (pin "35") (pinfunction "V12D_35") (pintype "power_in"))
      (node (ref "J11") (pin "37") (pinfunction "V12D_37") (pintype "power_in"))
      (node (ref "J11") (pin "39") (pinfunction "V12D_39") (pintype "power_in"))
      (node (ref "J11") (pin "41") (pinfunction "V12D_41") (pintype "power_in"))
      (node (ref "J11") (pin "43") (pinfunction "V12D_43") (pintype "power_in"))
      (node (ref "J11") (pin "45") (pinfunction "V12D_45") (pintype "power_in"))
      (node (ref "J11") (pin "47") (pinfunction "V12D_47") (pintype "power_in"))
      (node (ref "J11") (pin "49") (pinfunction "V12D_49") (pintype "power_in"))
      (node (ref "J12") (pin "27") (pinfunction "V12D_27") (pintype "power_in"))
      (node (ref "J12") (pin "29") (pinfunction "V12D_29") (pintype "power_in"))
      (node (ref "J12") (pin "31") (pinfunction "V12D_31") (pintype "power_in"))
      (node (ref "J12") (pin "33") (pinfunction "V12D_33") (pintype "power_in"))
      (node (ref "J12") (pin "35") (pinfunction "V12D_35") (pintype "power_in"))
      (node (ref "J12") (pin "37") (pinfunction "V12D_37") (pintype "power_in"))
      (node (ref "J12") (pin "39") (pinfunction "V12D_39") (pintype "power_in"))
      (node (ref "J12") (pin "41") (pinfunction "V12D_41") (pintype "power_in"))
      (node (ref "J12") (pin "43") (pinfunction "V12D_43") (pintype "power_in"))
      (node (ref "J12") (pin "45") (pinfunction "V12D_45") (pintype "power_in"))
      (node (ref "J12") (pin "47") (pinfunction "V12D_47") (pintype "power_in"))
      (node (ref "J12") (pin "49") (pinfunction "V12D_49") (pintype "power_in"))
      (node (ref "J7") (pin "27") (pinfunction "V12D_27") (pintype "power_in"))
      (node (ref "J7") (pin "29") (pinfunction "V12D_29") (pintype "power_in"))
      (node (ref "J7") (pin "31") (pinfunction "V12D_31") (pintype "power_in"))
      (node (ref "J7") (pin "33") (pinfunction "V12D_33") (pintype "power_in"))
      (node (ref "J7") (pin "35") (pinfunction "V12D_35") (pintype "power_in"))
      (node (ref "J7") (pin "37") (pinfunction "V12D_37") (pintype "power_in"))
      (node (ref "J7") (pin "39") (pinfunction "V12D_39") (pintype "power_in"))
      (node (ref "J7") (pin "41") (pinfunction "V12D_41") (pintype "power_in"))
      (node (ref "J7") (pin "43") (pinfunction "V12D_43") (pintype "power_in"))
      (node (ref "J7") (pin "45") (pinfunction "V12D_45") (pintype "power_in"))
      (node (ref "J7") (pin "47") (pinfunction "V12D_47") (pintype "power_in"))
      (node (ref "J7") (pin "49") (pinfunction "V12D_49") (pintype "power_in"))
      (node (ref "J8") (pin "27") (pinfunction "V12D_27") (pintype "power_in"))
      (node (ref "J8") (pin "29") (pinfunction "V12D_29") (pintype "power_in"))
      (node (ref "J8") (pin "31") (pinfunction "V12D_31") (pintype "power_in"))
      (node (ref "J8") (pin "33") (pinfunction "V12D_33") (pintype "power_in"))
      (node (ref "J8") (pin "35") (pinfunction "V12D_35") (pintype "power_in"))
      (node (ref "J8") (pin "37") (pinfunction "V12D_37") (pintype "power_in"))
      (node (ref "J8") (pin "39") (pinfunction "V12D_39") (pintype "power_in"))
      (node (ref "J8") (pin "41") (pinfunction "V12D_41") (pintype "power_in"))
      (node (ref "J8") (pin "43") (pinfunction "V12D_43") (pintype "power_in"))
      (node (ref "J8") (pin "45") (pinfunction "V12D_45") (pintype "power_in"))
      (node (ref "J8") (pin "47") (pinfunction "V12D_47") (pintype "power_in"))
      (node (ref "J8") (pin "49") (pinfunction "V12D_49") (pintype "power_in"))
      (node (ref "J9") (pin "27") (pinfunction "V12D_27") (pintype "power_in"))
      (node (ref "J9") (pin "29") (pinfunction "V12D_29") (pintype "power_in"))
      (node (ref "J9") (pin "31") (pinfunction "V12D_31") (pintype "power_in"))
      (node (ref "J9") (pin "33") (pinfunction "V12D_33") (pintype "power_in"))
      (node (ref "J9") (pin "35") (pinfunction "V12D_35") (pintype "power_in"))
      (node (ref "J9") (pin "37") (pinfunction "V12D_37") (pintype "power_in"))
      (node (ref "J9") (pin "39") (pinfunction "V12D_39") (pintype "power_in"))
      (node (ref "J9") (pin "41") (pinfunction "V12D_41") (pintype "power_in"))
      (node (ref "J9") (pin "43") (pinfunction "V12D_43") (pintype "power_in"))
      (node (ref "J9") (pin "45") (pinfunction "V12D_45") (pintype "power_in"))
      (node (ref "J9") (pin "47") (pinfunction "V12D_47") (pintype "power_in"))
      (node (ref "J9") (pin "49") (pinfunction "V12D_49") (pintype "power_in"))
    )
    (net (code "153") (name "DGND") (class "Default")
      (node (ref "C14") (pin "2") (pinfunction "2_2") (pintype "passive"))
      (node (ref "C16") (pin "2") (pinfunction "2_2") (pintype "passive"))
      (node (ref "C18") (pin "2") (pinfunction "2_2") (pintype "passive"))
      (node (ref "C20") (pin "2") (pinfunction "2_2") (pintype "passive"))
      (node (ref "C22") (pin "2") (pinfunction "2_2") (pintype "passive"))
      (node (ref "C24") (pin "2") (pinfunction "2_2") (pintype "passive"))
      (node (ref "J10") (pin "75") (pinfunction "DGND_75") (pintype "power_in"))
      (node (ref "J10") (pin "77") (pinfunction "DGND_77") (pintype "power_in"))
      (node (ref "J10") (pin "79") (pinfunction "DGND_79") (pintype "power_in"))
      (node (ref "J10") (pin "81") (pinfunction "DGND_81") (pintype "power_in"))
      (node (ref "J10") (pin "83") (pinfunction "DGND_83") (pintype "power_in"))
      (node (ref "J10") (pin "85") (pinfunction "DGND_85") (pintype "power_in"))
      (node (ref "J10") (pin "87") (pinfunction "DGND_87") (pintype "power_in"))
      (node (ref "J10") (pin "89") (pinfunction "DGND_89") (pintype "power_in"))
      (node (ref "J10") (pin "91") (pinfunction "DGND_91") (pintype "power_in"))
      (node (ref "J10") (pin "93") (pinfunction "DGND_93") (pintype "power_in"))
      (node (ref "J10") (pin "95") (pinfunction "DGND_95") (pintype "power_in"))
      (node (ref "J10") (pin "97") (pinfunction "DGND_97") (pintype "power_in"))
      (node (ref "J10") (pin "99") (pinfunction "DGND_99") (pintype "power_in"))
      (node (ref "J11") (pin "75") (pinfunction "DGND_75") (pintype "power_in"))
      (node (ref "J11") (pin "77") (pinfunction "DGND_77") (pintype "power_in"))
      (node (ref "J11") (pin "79") (pinfunction "DGND_79") (pintype "power_in"))
      (node (ref "J11") (pin "81") (pinfunction "DGND_81") (pintype "power_in"))
      (node (ref "J11") (pin "83") (pinfunction "DGND_83") (pintype "power_in"))
      (node (ref "J11") (pin "85") (pinfunction "DGND_85") (pintype "power_in"))
      (node (ref "J11") (pin "87") (pinfunction "DGND_87") (pintype "power_in"))
      (node (ref "J11") (pin "89") (pinfunction "DGND_89") (pintype "power_in"))
      (node (ref "J11") (pin "91") (pinfunction "DGND_91") (pintype "power_in"))
      (node (ref "J11") (pin "93") (pinfunction "DGND_93") (pintype "power_in"))
      (node (ref "J11") (pin "95") (pinfunction "DGND_95") (pintype "power_in"))
      (node (ref "J11") (pin "97") (pinfunction "DGND_97") (pintype "power_in"))
      (node (ref "J11") (pin "99") (pinfunction "DGND_99") (pintype "power_in"))
      (node (ref "J12") (pin "75") (pinfunction "DGND_75") (pintype "power_in"))
      (node (ref "J12") (pin "77") (pinfunction "DGND_77") (pintype "power_in"))
      (node (ref "J12") (pin "79") (pinfunction "DGND_79") (pintype "power_in"))
      (node (ref "J12") (pin "81") (pinfunction "DGND_81") (pintype "power_in"))
      (node (ref "J12") (pin "83") (pinfunction "DGND_83") (pintype "power_in"))
      (node (ref "J12") (pin "85") (pinfunction "DGND_85") (pintype "power_in"))
      (node (ref "J12") (pin "87") (pinfunction "DGND_87") (pintype "power_in"))
      (node (ref "J12") (pin "89") (pinfunction "DGND_89") (pintype "power_in"))
      (node (ref "J12") (pin "91") (pinfunction "DGND_91") (pintype "power_in"))
      (node (ref "J12") (pin "93") (pinfunction "DGND_93") (pintype "power_in"))
      (node (ref "J12") (pin "95") (pinfunction "DGND_95") (pintype "power_in"))
      (node (ref "J12") (pin "97") (pinfunction "DGND_97") (pintype "power_in"))
      (node (ref "J12") (pin "99") (pinfunction "DGND_99") (pintype "power_in"))
      (node (ref "J7") (pin "75") (pinfunction "DGND_75") (pintype "power_in"))
      (node (ref "J7") (pin "77") (pinfunction "DGND_77") (pintype "power_in"))
      (node (ref "J7") (pin "79") (pinfunction "DGND_79") (pintype "power_in"))
      (node (ref "J7") (pin "81") (pinfunction "DGND_81") (pintype "power_in"))
      (node (ref "J7") (pin "83") (pinfunction "DGND_83") (pintype "power_in"))
      (node (ref "J7") (pin "85") (pinfunction "DGND_85") (pintype "power_in"))
      (node (ref "J7") (pin "87") (pinfunction "DGND_87") (pintype "power_in"))
      (node (ref "J7") (pin "89") (pinfunction "DGND_89") (pintype "power_in"))
      (node (ref "J7") (pin "91") (pinfunction "DGND_91") (pintype "power_in"))
      (node (ref "J7") (pin "93") (pinfunction "DGND_93") (pintype "power_in"))
      (node (ref "J7") (pin "95") (pinfunction "DGND_95") (pintype "power_in"))
      (node (ref "J7") (pin "97") (pinfunction "DGND_97") (pintype "power_in"))
      (node (ref "J7") (pin "99") (pinfunction "DGND_99") (pintype "power_in"))
      (node (ref "J8") (pin "75") (pinfunction "DGND_75") (pintype "power_in"))
      (node (ref "J8") (pin "77") (pinfunction "DGND_77") (pintype "power_in"))
      (node (ref "J8") (pin "79") (pinfunction "DGND_79") (pintype "power_in"))
      (node (ref "J8") (pin "81") (pinfunction "DGND_81") (pintype "power_in"))
      (node (ref "J8") (pin "83") (pinfunction "DGND_83") (pintype "power_in"))
      (node (ref "J8") (pin "85") (pinfunction "DGND_85") (pintype "power_in"))
      (node (ref "J8") (pin "87") (pinfunction "DGND_87") (pintype "power_in"))
      (node (ref "J8") (pin "89") (pinfunction "DGND_89") (pintype "power_in"))
      (node (ref "J8") (pin "91") (pinfunction "DGND_91") (pintype "power_in"))
      (node (ref "J8") (pin "93") (pinfunction "DGND_93") (pintype "power_in"))
      (node (ref "J8") (pin "95") (pinfunction "DGND_95") (pintype "power_in"))
      (node (ref "J8") (pin "97") (pinfunction "DGND_97") (pintype "power_in"))
      (node (ref "J8") (pin "99") (pinfunction "DGND_99") (pintype "power_in"))
      (node (ref "J9") (pin "75") (pinfunction "DGND_75") (pintype "power_in"))
      (node (ref "J9") (pin "77") (pinfunction "DGND_77") (pintype "power_in"))
      (node (ref "J9") (pin "79") (pinfunction "DGND_79") (pintype "power_in"))
      (node (ref "J9") (pin "81") (pinfunction "DGND_81") (pintype "power_in"))
      (node (ref "J9") (pin "83") (pinfunction "DGND_83") (pintype "power_in"))
      (node (ref "J9") (pin "85") (pinfunction "DGND_85") (pintype "power_in"))
      (node (ref "J9") (pin "87") (pinfunction "DGND_87") (pintype "power_in"))
      (node (ref "J9") (pin "89") (pinfunction "DGND_89") (pintype "power_in"))
      (node (ref "J9") (pin "91") (pinfunction "DGND_91") (pintype "power_in"))
      (node (ref "J9") (pin "93") (pinfunction "DGND_93") (pintype "power_in"))
      (node (ref "J9") (pin "95") (pinfunction "DGND_95") (pintype "power_in"))
      (node (ref "J9") (pin "97") (pinfunction "DGND_97") (pintype "power_in"))
      (node (ref "J9") (pin "99") (pinfunction "DGND_99") (pintype "power_in"))
      (node (ref "OH_CONN2") (pin "10") (pinfunction "DGND_10") (pintype "power_in"))
      (node (ref "OH_CONN2") (pin "11") (pinfunction "DGND_11") (pintype "power_in"))
      (node (ref "OH_CONN2") (pin "12") (pinfunction "DGND_12") (pintype "power_in"))
      (node (ref "OH_CONN2") (pin "161") (pinfunction "Bank01_161") (pintype "passive"))
      (node (ref "OH_CONN2") (pin "162") (pinfunction "Bank02_162") (pintype "passive"))
      (node (ref "OH_CONN2") (pin "163") (pinfunction "Bank03_163") (pintype "passive"))
      (node (ref "OH_CONN2") (pin "164") (pinfunction "Bank04_164") (pintype "passive"))
      (node (ref "OH_CONN2") (pin "169") (pinfunction "Bank21_169") (pintype "passive"))
      (node (ref "OH_CONN2") (pin "170") (pinfunction "Bank22_170") (pintype "passive"))
      (node (ref "OH_CONN2") (pin "171") (pinfunction "Bank23_171") (pintype "passive"))
      (node (ref "OH_CONN2") (pin "172") (pinfunction "Bank24_172") (pintype "passive"))
      (node (ref "OH_CONN2") (pin "61") (pinfunction "DGND_61") (pintype "power_in"))
      (node (ref "OH_CONN2") (pin "62") (pinfunction "DGND_62") (pintype "power_in"))
      (node (ref "OH_CONN2") (pin "63") (pinfunction "DGND_63") (pintype "power_in"))
      (node (ref "OH_CONN2") (pin "64") (pinfunction "DGND_64") (pintype "power_in"))
      (node (ref "OH_CONN2") (pin "9") (pinfunction "DGND_9") (pintype "power_in"))
    )
    (net (code "154") (name "Monitor4") (class "Default")
      (node (ref "OH_CONN2") (pin "7") (pinfunction "MONITOR4_7") (pintype "input"))
    )
    (net (code "155") (name "Monitor5") (class "Default")
      (node (ref "OH_CONN2") (pin "8") (pinfunction "MONITOR5_8") (pintype "input"))
    )
    (net (code "156") (name "PWR1V8") (class "Default")
      (node (ref "OH_CONN2") (pin "173") (pinfunction "Bank31_173") (pintype "passive"))
      (node (ref "OH_CONN2") (pin "174") (pinfunction "Bank32_174") (pintype "passive"))
      (node (ref "OH_CONN2") (pin "175") (pinfunction "Bank33_175") (pintype "passive"))
      (node (ref "OH_CONN2") (pin "176") (pinfunction "Bank34_176") (pintype "passive"))
    )
    (net (code "157") (name "PWR2V5") (class "Default")
      (node (ref "OH_CONN2") (pin "165") (pinfunction "Bank11_165") (pintype "passive"))
      (node (ref "OH_CONN2") (pin "166") (pinfunction "Bank12_166") (pintype "passive"))
      (node (ref "OH_CONN2") (pin "167") (pinfunction "Bank13_167") (pintype "passive"))
      (node (ref "OH_CONN2") (pin "168") (pinfunction "Bank14_168") (pintype "passive"))
    )
    (net (code "158") (name "VFATAGND2") (class "Default")
      (node (ref "C13") (pin "2") (pinfunction "2_2") (pintype "passive"))
      (node (ref "C15") (pin "2") (pinfunction "2_2") (pintype "passive"))
      (node (ref "C17") (pin "2") (pinfunction "2_2") (pintype "passive"))
      (node (ref "C19") (pin "2") (pinfunction "2_2") (pintype "passive"))
      (node (ref "C21") (pin "2") (pinfunction "2_2") (pintype "passive"))
      (node (ref "C23") (pin "2") (pinfunction "2_2") (pintype "passive"))
      (node (ref "J10") (pin "51") (pinfunction "AGND_51") (pintype "power_in"))
      (node (ref "J10") (pin "53") (pinfunction "AGND_53") (pintype "power_in"))
      (node (ref "J10") (pin "55") (pinfunction "AGND_55") (pintype "power_in"))
      (node (ref "J10") (pin "57") (pinfunction "AGND_57") (pintype "power_in"))
      (node (ref "J10") (pin "59") (pinfunction "AGND_59") (pintype "power_in"))
      (node (ref "J10") (pin "61") (pinfunction "AGND_61") (pintype "power_in"))
      (node (ref "J10") (pin "63") (pinfunction "AGND_63") (pintype "power_in"))
      (node (ref "J10") (pin "65") (pinfunction "AGND_65") (pintype "power_in"))
      (node (ref "J10") (pin "67") (pinfunction "AGND_67") (pintype "power_in"))
      (node (ref "J10") (pin "69") (pinfunction "AGND_69") (pintype "power_in"))
      (node (ref "J10") (pin "71") (pinfunction "AGND_71") (pintype "power_in"))
      (node (ref "J10") (pin "73") (pinfunction "AGND_73") (pintype "power_in"))
      (node (ref "J11") (pin "51") (pinfunction "AGND_51") (pintype "power_in"))
      (node (ref "J11") (pin "53") (pinfunction "AGND_53") (pintype "power_in"))
      (node (ref "J11") (pin "55") (pinfunction "AGND_55") (pintype "power_in"))
      (node (ref "J11") (pin "57") (pinfunction "AGND_57") (pintype "power_in"))
      (node (ref "J11") (pin "59") (pinfunction "AGND_59") (pintype "power_in"))
      (node (ref "J11") (pin "61") (pinfunction "AGND_61") (pintype "power_in"))
      (node (ref "J11") (pin "63") (pinfunction "AGND_63") (pintype "power_in"))
      (node (ref "J11") (pin "65") (pinfunction "AGND_65") (pintype "power_in"))
      (node (ref "J11") (pin "67") (pinfunction "AGND_67") (pintype "power_in"))
      (node (ref "J11") (pin "69") (pinfunction "AGND_69") (pintype "power_in"))
      (node (ref "J11") (pin "71") (pinfunction "AGND_71") (pintype "power_in"))
      (node (ref "J11") (pin "73") (pinfunction "AGND_73") (pintype "power_in"))
      (node (ref "J12") (pin "51") (pinfunction "AGND_51") (pintype "power_in"))
      (node (ref "J12") (pin "53") (pinfunction "AGND_53") (pintype "power_in"))
      (node (ref "J12") (pin "55") (pinfunction "AGND_55") (pintype "power_in"))
      (node (ref "J12") (pin "57") (pinfunction "AGND_57") (pintype "power_in"))
      (node (ref "J12") (pin "59") (pinfunction "AGND_59") (pintype "power_in"))
      (node (ref "J12") (pin "61") (pinfunction "AGND_61") (pintype "power_in"))
      (node (ref "J12") (pin "63") (pinfunction "AGND_63") (pintype "power_in"))
      (node (ref "J12") (pin "65") (pinfunction "AGND_65") (pintype "power_in"))
      (node (ref "J12") (pin "67") (pinfunction "AGND_67") (pintype "power_in"))
      (node (ref "J12") (pin "69") (pinfunction "AGND_69") (pintype "power_in"))
      (node (ref "J12") (pin "71") (pinfunction "AGND_71") (pintype "power_in"))
      (node (ref "J12") (pin "73") (pinfunction "AGND_73") (pintype "power_in"))
      (node (ref "J7") (pin "51") (pinfunction "AGND_51") (pintype "power_in"))
      (node (ref "J7") (pin "53") (pinfunction "AGND_53") (pintype "power_in"))
      (node (ref "J7") (pin "55") (pinfunction "AGND_55") (pintype "power_in"))
      (node (ref "J7") (pin "57") (pinfunction "AGND_57") (pintype "power_in"))
      (node (ref "J7") (pin "59") (pinfunction "AGND_59") (pintype "power_in"))
      (node (ref "J7") (pin "61") (pinfunction "AGND_61") (pintype "power_in"))
      (node (ref "J7") (pin "63") (pinfunction "AGND_63") (pintype "power_in"))
      (node (ref "J7") (pin "65") (pinfunction "AGND_65") (pintype "power_in"))
      (node (ref "J7") (pin "67") (pinfunction "AGND_67") (pintype "power_in"))
      (node (ref "J7") (pin "69") (pinfunction "AGND_69") (pintype "power_in"))
      (node (ref "J7") (pin "71") (pinfunction "AGND_71") (pintype "power_in"))
      (node (ref "J7") (pin "73") (pinfunction "AGND_73") (pintype "power_in"))
      (node (ref "J8") (pin "51") (pinfunction "AGND_51") (pintype "power_in"))
      (node (ref "J8") (pin "53") (pinfunction "AGND_53") (pintype "power_in"))
      (node (ref "J8") (pin "55") (pinfunction "AGND_55") (pintype "power_in"))
      (node (ref "J8") (pin "57") (pinfunction "AGND_57") (pintype "power_in"))
      (node (ref "J8") (pin "59") (pinfunction "AGND_59") (pintype "power_in"))
      (node (ref "J8") (pin "61") (pinfunction "AGND_61") (pintype "power_in"))
      (node (ref "J8") (pin "63") (pinfunction "AGND_63") (pintype "power_in"))
      (node (ref "J8") (pin "65") (pinfunction "AGND_65") (pintype "power_in"))
      (node (ref "J8") (pin "67") (pinfunction "AGND_67") (pintype "power_in"))
      (node (ref "J8") (pin "69") (pinfunction "AGND_69") (pintype "power_in"))
      (node (ref "J8") (pin "71") (pinfunction "AGND_71") (pintype "power_in"))
      (node (ref "J8") (pin "73") (pinfunction "AGND_73") (pintype "power_in"))
      (node (ref "J9") (pin "51") (pinfunction "AGND_51") (pintype "power_in"))
      (node (ref "J9") (pin "53") (pinfunction "AGND_53") (pintype "power_in"))
      (node (ref "J9") (pin "55") (pinfunction "AGND_55") (pintype "power_in"))
      (node (ref "J9") (pin "57") (pinfunction "AGND_57") (pintype "power_in"))
      (node (ref "J9") (pin "59") (pinfunction "AGND_59") (pintype "power_in"))
      (node (ref "J9") (pin "61") (pinfunction "AGND_61") (pintype "power_in"))
      (node (ref "J9") (pin "63") (pinfunction "AGND_63") (pintype "power_in"))
      (node (ref "J9") (pin "65") (pinfunction "AGND_65") (pintype "power_in"))
      (node (ref "J9") (pin "67") (pinfunction "AGND_67") (pintype "power_in"))
      (node (ref "J9") (pin "69") (pinfunction "AGND_69") (pintype "power_in"))
      (node (ref "J9") (pin "71") (pinfunction "AGND_71") (pintype "power_in"))
      (node (ref "J9") (pin "73") (pinfunction "AGND_73") (pintype "power_in"))
    )
    (net (code "159") (name "unconnected-(J7-Pad2)") (class "Default")
      (node (ref "J7") (pin "2") (pinfunction "2_2") (pintype "passive"))
    )
    (net (code "160") (name "unconnected-(J7-Pad4)") (class "Default")
      (node (ref "J7") (pin "4") (pinfunction "4_4") (pintype "passive"))
    )
    (net (code "161") (name "unconnected-(J7-Pad6)") (class "Default")
      (node (ref "J7") (pin "6") (pinfunction "6_6") (pintype "passive"))
    )
    (net (code "162") (name "unconnected-(J7-Pad8)") (class "Default")
      (node (ref "J7") (pin "8") (pinfunction "8_8") (pintype "passive"))
    )
    (net (code "163") (name "unconnected-(J7-Pad10)") (class "Default")
      (node (ref "J7") (pin "10") (pinfunction "10_10") (pintype "passive"))
    )
    (net (code "164") (name "unconnected-(J7-Pad12)") (class "Default")
      (node (ref "J7") (pin "12") (pinfunction "12_12") (pintype "passive"))
    )
    (net (code "165") (name "unconnected-(J7-Pad14)") (class "Default")
      (node (ref "J7") (pin "14") (pinfunction "14_14") (pintype "passive"))
    )
    (net (code "166") (name "unconnected-(J7-Pad16)") (class "Default")
      (node (ref "J7") (pin "16") (pinfunction "16_16") (pintype "passive"))
    )
    (net (code "167") (name "unconnected-(J7-Pad18)") (class "Default")
      (node (ref "J7") (pin "18") (pinfunction "18_18") (pintype "passive"))
    )
    (net (code "168") (name "unconnected-(J7-Pad20)") (class "Default")
      (node (ref "J7") (pin "20") (pinfunction "20_20") (pintype "passive"))
    )
    (net (code "169") (name "unconnected-(J7-Pad22)") (class "Default")
      (node (ref "J7") (pin "22") (pinfunction "22_22") (pintype "passive"))
    )
    (net (code "170") (name "unconnected-(J7-Pad24)") (class "Default")
      (node (ref "J7") (pin "24") (pinfunction "24_24") (pintype "passive"))
    )
    (net (code "171") (name "unconnected-(J7-Pad26)") (class "Default")
      (node (ref "J7") (pin "26") (pinfunction "26_26") (pintype "passive"))
    )
    (net (code "172") (name "unconnected-(J7-Pad28)") (class "Default")
      (node (ref "J7") (pin "28") (pinfunction "28_28") (pintype "passive"))
    )
    (net (code "173") (name "unconnected-(J7-Pad30)") (class "Default")
      (node (ref "J7") (pin "30") (pinfunction "30_30") (pintype "passive"))
    )
    (net (code "174") (name "unconnected-(J7-Pad32)") (class "Default")
      (node (ref "J7") (pin "32") (pinfunction "32_32") (pintype "passive"))
    )
    (net (code "175") (name "unconnected-(J7-Pad34)") (class "Default")
      (node (ref "J7") (pin "34") (pinfunction "34_34") (pintype "passive"))
    )
    (net (code "176") (name "unconnected-(J7-Pad36)") (class "Default")
      (node (ref "J7") (pin "36") (pinfunction "36_36") (pintype "passive"))
    )
    (net (code "177") (name "unconnected-(J7-Pad38)") (class "Default")
      (node (ref "J7") (pin "38") (pinfunction "38_38") (pintype "passive"))
    )
    (net (code "178") (name "unconnected-(J7-Pad40)") (class "Default")
      (node (ref "J7") (pin "40") (pinfunction "40_40") (pintype "passive"))
    )
    (net (code "179") (name "unconnected-(J7-Pad42)") (class "Default")
      (node (ref "J7") (pin "42") (pinfunction "42_42") (pintype "passive"))
    )
    (net (code "180") (name "unconnected-(J7-Pad44)") (class "Default")
      (node (ref "J7") (pin "44") (pinfunction "44_44") (pintype "passive"))
    )
    (net (code "181") (name "unconnected-(J7-Pad46)") (class "Default")
      (node (ref "J7") (pin "46") (pinfunction "46_46") (pintype "passive"))
    )
    (net (code "182") (name "unconnected-(J7-Pad48)") (class "Default")
      (node (ref "J7") (pin "48") (pinfunction "48_48") (pintype "passive"))
    )
    (net (code "183") (name "unconnected-(J7-Pad50)") (class "Default")
      (node (ref "J7") (pin "50") (pinfunction "50_50") (pintype "passive"))
    )
    (net (code "184") (name "unconnected-(J8-Pad2)") (class "Default")
      (node (ref "J8") (pin "2") (pinfunction "2_2") (pintype "passive"))
    )
    (net (code "185") (name "unconnected-(J8-Pad4)") (class "Default")
      (node (ref "J8") (pin "4") (pinfunction "4_4") (pintype "passive"))
    )
    (net (code "186") (name "unconnected-(J8-Pad6)") (class "Default")
      (node (ref "J8") (pin "6") (pinfunction "6_6") (pintype "passive"))
    )
    (net (code "187") (name "unconnected-(J8-Pad8)") (class "Default")
      (node (ref "J8") (pin "8") (pinfunction "8_8") (pintype "passive"))
    )
    (net (code "188") (name "unconnected-(J8-Pad10)") (class "Default")
      (node (ref "J8") (pin "10") (pinfunction "10_10") (pintype "passive"))
    )
    (net (code "189") (name "unconnected-(J8-Pad12)") (class "Default")
      (node (ref "J8") (pin "12") (pinfunction "12_12") (pintype "passive"))
    )
    (net (code "190") (name "unconnected-(J8-Pad14)") (class "Default")
      (node (ref "J8") (pin "14") (pinfunction "14_14") (pintype "passive"))
    )
    (net (code "191") (name "unconnected-(J8-Pad16)") (class "Default")
      (node (ref "J8") (pin "16") (pinfunction "16_16") (pintype "passive"))
    )
    (net (code "192") (name "unconnected-(J8-Pad18)") (class "Default")
      (node (ref "J8") (pin "18") (pinfunction "18_18") (pintype "passive"))
    )
    (net (code "193") (name "unconnected-(J8-Pad20)") (class "Default")
      (node (ref "J8") (pin "20") (pinfunction "20_20") (pintype "passive"))
    )
    (net (code "194") (name "unconnected-(J8-Pad22)") (class "Default")
      (node (ref "J8") (pin "22") (pinfunction "22_22") (pintype "passive"))
    )
    (net (code "195") (name "unconnected-(J8-Pad24)") (class "Default")
      (node (ref "J8") (pin "24") (pinfunction "24_24") (pintype "passive"))
    )
    (net (code "196") (name "unconnected-(J8-Pad26)") (class "Default")
      (node (ref "J8") (pin "26") (pinfunction "26_26") (pintype "passive"))
    )
    (net (code "197") (name "unconnected-(J8-Pad28)") (class "Default")
      (node (ref "J8") (pin "28") (pinfunction "28_28") (pintype "passive"))
    )
    (net (code "198") (name "unconnected-(J8-Pad30)") (class "Default")
      (node (ref "J8") (pin "30") (pinfunction "30_30") (pintype "passive"))
    )
    (net (code "199") (name "unconnected-(J8-Pad32)") (class "Default")
      (node (ref "J8") (pin "32") (pinfunction "32_32") (pintype "passive"))
    )
    (net (code "200") (name "unconnected-(J8-Pad34)") (class "Default")
      (node (ref "J8") (pin "34") (pinfunction "34_34") (pintype "passive"))
    )
    (net (code "201") (name "unconnected-(J8-Pad36)") (class "Default")
      (node (ref "J8") (pin "36") (pinfunction "36_36") (pintype "passive"))
    )
    (net (code "202") (name "unconnected-(J8-Pad38)") (class "Default")
      (node (ref "J8") (pin "38") (pinfunction "38_38") (pintype "passive"))
    )
    (net (code "203") (name "unconnected-(J8-Pad40)") (class "Default")
      (node (ref "J8") (pin "40") (pinfunction "40_40") (pintype "passive"))
    )
    (net (code "204") (name "unconnected-(J8-Pad42)") (class "Default")
      (node (ref "J8") (pin "42") (pinfunction "42_42") (pintype "passive"))
    )
    (net (code "205") (name "unconnected-(J8-Pad44)") (class "Default")
      (node (ref "J8") (pin "44") (pinfunction "44_44") (pintype "passive"))
    )
    (net (code "206") (name "unconnected-(J8-Pad46)") (class "Default")
      (node (ref "J8") (pin "46") (pinfunction "46_46") (pintype "passive"))
    )
    (net (code "207") (name "unconnected-(J8-Pad48)") (class "Default")
      (node (ref "J8") (pin "48") (pinfunction "48_48") (pintype "passive"))
    )
    (net (code "208") (name "unconnected-(J8-Pad50)") (class "Default")
      (node (ref "J8") (pin "50") (pinfunction "50_50") (pintype "passive"))
    )
    (net (code "209") (name "unconnected-(J9-Pad2)") (class "Default")
      (node (ref "J9") (pin "2") (pinfunction "2_2") (pintype "passive"))
    )
    (net (code "210") (name "unconnected-(J9-Pad4)") (class "Default")
      (node (ref "J9") (pin "4") (pinfunction "4_4") (pintype "passive"))
    )
    (net (code "211") (name "unconnected-(J9-Pad6)") (class "Default")
      (node (ref "J9") (pin "6") (pinfunction "6_6") (pintype "passive"))
    )
    (net (code "212") (name "unconnected-(J9-Pad8)") (class "Default")
      (node (ref "J9") (pin "8") (pinfunction "8_8") (pintype "passive"))
    )
    (net (code "213") (name "unconnected-(J9-Pad10)") (class "Default")
      (node (ref "J9") (pin "10") (pinfunction "10_10") (pintype "passive"))
    )
    (net (code "214") (name "unconnected-(J9-Pad12)") (class "Default")
      (node (ref "J9") (pin "12") (pinfunction "12_12") (pintype "passive"))
    )
    (net (code "215") (name "unconnected-(J9-Pad14)") (class "Default")
      (node (ref "J9") (pin "14") (pinfunction "14_14") (pintype "passive"))
    )
    (net (code "216") (name "unconnected-(J9-Pad16)") (class "Default")
      (node (ref "J9") (pin "16") (pinfunction "16_16") (pintype "passive"))
    )
    (net (code "217") (name "unconnected-(J9-Pad18)") (class "Default")
      (node (ref "J9") (pin "18") (pinfunction "18_18") (pintype "passive"))
    )
    (net (code "218") (name "unconnected-(J9-Pad20)") (class "Default")
      (node (ref "J9") (pin "20") (pinfunction "20_20") (pintype "passive"))
    )
    (net (code "219") (name "unconnected-(J9-Pad22)") (class "Default")
      (node (ref "J9") (pin "22") (pinfunction "22_22") (pintype "passive"))
    )
    (net (code "220") (name "unconnected-(J9-Pad24)") (class "Default")
      (node (ref "J9") (pin "24") (pinfunction "24_24") (pintype "passive"))
    )
    (net (code "221") (name "unconnected-(J9-Pad26)") (class "Default")
      (node (ref "J9") (pin "26") (pinfunction "26_26") (pintype "passive"))
    )
    (net (code "222") (name "unconnected-(J9-Pad28)") (class "Default")
      (node (ref "J9") (pin "28") (pinfunction "28_28") (pintype "passive"))
    )
    (net (code "223") (name "unconnected-(J9-Pad30)") (class "Default")
      (node (ref "J9") (pin "30") (pinfunction "30_30") (pintype "passive"))
    )
    (net (code "224") (name "unconnected-(J9-Pad32)") (class "Default")
      (node (ref "J9") (pin "32") (pinfunction "32_32") (pintype "passive"))
    )
    (net (code "225") (name "unconnected-(J9-Pad34)") (class "Default")
      (node (ref "J9") (pin "34") (pinfunction "34_34") (pintype "passive"))
    )
    (net (code "226") (name "unconnected-(J9-Pad36)") (class "Default")
      (node (ref "J9") (pin "36") (pinfunction "36_36") (pintype "passive"))
    )
    (net (code "227") (name "unconnected-(J9-Pad38)") (class "Default")
      (node (ref "J9") (pin "38") (pinfunction "38_38") (pintype "passive"))
    )
    (net (code "228") (name "unconnected-(J9-Pad40)") (class "Default")
      (node (ref "J9") (pin "40") (pinfunction "40_40") (pintype "passive"))
    )
    (net (code "229") (name "unconnected-(J9-Pad42)") (class "Default")
      (node (ref "J9") (pin "42") (pinfunction "42_42") (pintype "passive"))
    )
    (net (code "230") (name "unconnected-(J9-Pad44)") (class "Default")
      (node (ref "J9") (pin "44") (pinfunction "44_44") (pintype "passive"))
    )
    (net (code "231") (name "unconnected-(J9-Pad46)") (class "Default")
      (node (ref "J9") (pin "46") (pinfunction "46_46") (pintype "passive"))
    )
    (net (code "232") (name "unconnected-(J9-Pad48)") (class "Default")
      (node (ref "J9") (pin "48") (pinfunction "48_48") (pintype "passive"))
    )
    (net (code "233") (name "unconnected-(J9-Pad50)") (class "Default")
      (node (ref "J9") (pin "50") (pinfunction "50_50") (pintype "passive"))
    )
    (net (code "234") (name "unconnected-(J10-Pad2)") (class "Default")
      (node (ref "J10") (pin "2") (pinfunction "2_2") (pintype "passive"))
    )
    (net (code "235") (name "unconnected-(J10-Pad4)") (class "Default")
      (node (ref "J10") (pin "4") (pinfunction "4_4") (pintype "passive"))
    )
    (net (code "236") (name "unconnected-(J10-Pad6)") (class "Default")
      (node (ref "J10") (pin "6") (pinfunction "6_6") (pintype "passive"))
    )
    (net (code "237") (name "unconnected-(J10-Pad8)") (class "Default")
      (node (ref "J10") (pin "8") (pinfunction "8_8") (pintype "passive"))
    )
    (net (code "238") (name "unconnected-(J10-Pad10)") (class "Default")
      (node (ref "J10") (pin "10") (pinfunction "10_10") (pintype "passive"))
    )
    (net (code "239") (name "unconnected-(J10-Pad12)") (class "Default")
      (node (ref "J10") (pin "12") (pinfunction "12_12") (pintype "passive"))
    )
    (net (code "240") (name "unconnected-(J10-Pad14)") (class "Default")
      (node (ref "J10") (pin "14") (pinfunction "14_14") (pintype "passive"))
    )
    (net (code "241") (name "unconnected-(J10-Pad16)") (class "Default")
      (node (ref "J10") (pin "16") (pinfunction "16_16") (pintype "passive"))
    )
    (net (code "242") (name "unconnected-(J10-Pad18)") (class "Default")
      (node (ref "J10") (pin "18") (pinfunction "18_18") (pintype "passive"))
    )
    (net (code "243") (name "unconnected-(J10-Pad20)") (class "Default")
      (node (ref "J10") (pin "20") (pinfunction "20_20") (pintype "passive"))
    )
    (net (code "244") (name "unconnected-(J10-Pad22)") (class "Default")
      (node (ref "J10") (pin "22") (pinfunction "22_22") (pintype "passive"))
    )
    (net (code "245") (name "unconnected-(J10-Pad24)") (class "Default")
      (node (ref "J10") (pin "24") (pinfunction "24_24") (pintype "passive"))
    )
    (net (code "246") (name "unconnected-(J10-Pad26)") (class "Default")
      (node (ref "J10") (pin "26") (pinfunction "26_26") (pintype "passive"))
    )
    (net (code "247") (name "unconnected-(J10-Pad28)") (class "Default")
      (node (ref "J10") (pin "28") (pinfunction "28_28") (pintype "passive"))
    )
    (net (code "248") (name "unconnected-(J10-Pad30)") (class "Default")
      (node (ref "J10") (pin "30") (pinfunction "30_30") (pintype "passive"))
    )
    (net (code "249") (name "unconnected-(J10-Pad32)") (class "Default")
      (node (ref "J10") (pin "32") (pinfunction "32_32") (pintype "passive"))
    )
    (net (code "250") (name "unconnected-(J10-Pad34)") (class "Default")
      (node (ref "J10") (pin "34") (pinfunction "34_34") (pintype "passive"))
    )
    (net (code "251") (name "unconnected-(J10-Pad36)") (class "Default")
      (node (ref "J10") (pin "36") (pinfunction "36_36") (pintype "passive"))
    )
    (net (code "252") (name "unconnected-(J10-Pad38)") (class "Default")
      (node (ref "J10") (pin "38") (pinfunction "38_38") (pintype "passive"))
    )
    (net (code "253") (name "unconnected-(J10-Pad40)") (class "Default")
      (node (ref "J10") (pin "40") (pinfunction "40_40") (pintype "passive"))
    )
    (net (code "254") (name "unconnected-(J10-Pad42)") (class "Default")
      (node (ref "J10") (pin "42") (pinfunction "42_42") (pintype "passive"))
    )
    (net (code "255") (name "unconnected-(J10-Pad44)") (class "Default")
      (node (ref "J10") (pin "44") (pinfunction "44_44") (pintype "passive"))
    )
    (net (code "256") (name "unconnected-(J10-Pad46)") (class "Default")
      (node (ref "J10") (pin "46") (pinfunction "46_46") (pintype "passive"))
    )
    (net (code "257") (name "unconnected-(J10-Pad48)") (class "Default")
      (node (ref "J10") (pin "48") (pinfunction "48_48") (pintype "passive"))
    )
    (net (code "258") (name "unconnected-(J10-Pad50)") (class "Default")
      (node (ref "J10") (pin "50") (pinfunction "50_50") (pintype "passive"))
    )
    (net (code "259") (name "unconnected-(J11-Pad2)") (class "Default")
      (node (ref "J11") (pin "2") (pinfunction "2_2") (pintype "passive"))
    )
    (net (code "260") (name "unconnected-(J11-Pad4)") (class "Default")
      (node (ref "J11") (pin "4") (pinfunction "4_4") (pintype "passive"))
    )
    (net (code "261") (name "unconnected-(J11-Pad6)") (class "Default")
      (node (ref "J11") (pin "6") (pinfunction "6_6") (pintype "passive"))
    )
    (net (code "262") (name "unconnected-(J11-Pad8)") (class "Default")
      (node (ref "J11") (pin "8") (pinfunction "8_8") (pintype "passive"))
    )
    (net (code "263") (name "unconnected-(J11-Pad10)") (class "Default")
      (node (ref "J11") (pin "10") (pinfunction "10_10") (pintype "passive"))
    )
    (net (code "264") (name "unconnected-(J11-Pad12)") (class "Default")
      (node (ref "J11") (pin "12") (pinfunction "12_12") (pintype "passive"))
    )
    (net (code "265") (name "unconnected-(J11-Pad14)") (class "Default")
      (node (ref "J11") (pin "14") (pinfunction "14_14") (pintype "passive"))
    )
    (net (code "266") (name "unconnected-(J11-Pad16)") (class "Default")
      (node (ref "J11") (pin "16") (pinfunction "16_16") (pintype "passive"))
    )
    (net (code "267") (name "unconnected-(J11-Pad18)") (class "Default")
      (node (ref "J11") (pin "18") (pinfunction "18_18") (pintype "passive"))
    )
    (net (code "268") (name "unconnected-(J11-Pad20)") (class "Default")
      (node (ref "J11") (pin "20") (pinfunction "20_20") (pintype "passive"))
    )
    (net (code "269") (name "unconnected-(J11-Pad22)") (class "Default")
      (node (ref "J11") (pin "22") (pinfunction "22_22") (pintype "passive"))
    )
    (net (code "270") (name "unconnected-(J11-Pad24)") (class "Default")
      (node (ref "J11") (pin "24") (pinfunction "24_24") (pintype "passive"))
    )
    (net (code "271") (name "unconnected-(J11-Pad26)") (class "Default")
      (node (ref "J11") (pin "26") (pinfunction "26_26") (pintype "passive"))
    )
    (net (code "272") (name "unconnected-(J11-Pad28)") (class "Default")
      (node (ref "J11") (pin "28") (pinfunction "28_28") (pintype "passive"))
    )
    (net (code "273") (name "unconnected-(J11-Pad30)") (class "Default")
      (node (ref "J11") (pin "30") (pinfunction "30_30") (pintype "passive"))
    )
    (net (code "274") (name "unconnected-(J11-Pad32)") (class "Default")
      (node (ref "J11") (pin "32") (pinfunction "32_32") (pintype "passive"))
    )
    (net (code "275") (name "unconnected-(J11-Pad34)") (class "Default")
      (node (ref "J11") (pin "34") (pinfunction "34_34") (pintype "passive"))
    )
    (net (code "276") (name "unconnected-(J11-Pad36)") (class "Default")
      (node (ref "J11") (pin "36") (pinfunction "36_36") (pintype "passive"))
    )
    (net (code "277") (name "unconnected-(J11-Pad38)") (class "Default")
      (node (ref "J11") (pin "38") (pinfunction "38_38") (pintype "passive"))
    )
    (net (code "278") (name "unconnected-(J11-Pad40)") (class "Default")
      (node (ref "J11") (pin "40") (pinfunction "40_40") (pintype "passive"))
    )
    (net (code "279") (name "unconnected-(J11-Pad42)") (class "Default")
      (node (ref "J11") (pin "42") (pinfunction "42_42") (pintype "passive"))
    )
    (net (code "280") (name "unconnected-(J11-Pad44)") (class "Default")
      (node (ref "J11") (pin "44") (pinfunction "44_44") (pintype "passive"))
    )
    (net (code "281") (name "unconnected-(J11-Pad46)") (class "Default")
      (node (ref "J11") (pin "46") (pinfunction "46_46") (pintype "passive"))
    )
    (net (code "282") (name "unconnected-(J11-Pad48)") (class "Default")
      (node (ref "J11") (pin "48") (pinfunction "48_48") (pintype "passive"))
    )
    (net (code "283") (name "unconnected-(J11-Pad50)") (class "Default")
      (node (ref "J11") (pin "50") (pinfunction "50_50") (pintype "passive"))
    )
    (net (code "284") (name "unconnected-(J12-Pad2)") (class "Default")
      (node (ref "J12") (pin "2") (pinfunction "2_2") (pintype "passive"))
    )
    (net (code "285") (name "unconnected-(J12-Pad4)") (class "Default")
      (node (ref "J12") (pin "4") (pinfunction "4_4") (pintype "passive"))
    )
    (net (code "286") (name "unconnected-(J12-Pad6)") (class "Default")
      (node (ref "J12") (pin "6") (pinfunction "6_6") (pintype "passive"))
    )
    (net (code "287") (name "unconnected-(J12-Pad8)") (class "Default")
      (node (ref "J12") (pin "8") (pinfunction "8_8") (pintype "passive"))
    )
    (net (code "288") (name "unconnected-(J12-Pad10)") (class "Default")
      (node (ref "J12") (pin "10") (pinfunction "10_10") (pintype "passive"))
    )
    (net (code "289") (name "unconnected-(J12-Pad12)") (class "Default")
      (node (ref "J12") (pin "12") (pinfunction "12_12") (pintype "passive"))
    )
    (net (code "290") (name "unconnected-(J12-Pad14)") (class "Default")
      (node (ref "J12") (pin "14") (pinfunction "14_14") (pintype "passive"))
    )
    (net (code "291") (name "unconnected-(J12-Pad16)") (class "Default")
      (node (ref "J12") (pin "16") (pinfunction "16_16") (pintype "passive"))
    )
    (net (code "292") (name "unconnected-(J12-Pad18)") (class "Default")
      (node (ref "J12") (pin "18") (pinfunction "18_18") (pintype "passive"))
    )
    (net (code "293") (name "unconnected-(J12-Pad20)") (class "Default")
      (node (ref "J12") (pin "20") (pinfunction "20_20") (pintype "passive"))
    )
    (net (code "294") (name "unconnected-(J12-Pad22)") (class "Default")
      (node (ref "J12") (pin "22") (pinfunction "22_22") (pintype "passive"))
    )
    (net (code "295") (name "unconnected-(J12-Pad24)") (class "Default")
      (node (ref "J12") (pin "24") (pinfunction "24_24") (pintype "passive"))
    )
    (net (code "296") (name "unconnected-(J12-Pad26)") (class "Default")
      (node (ref "J12") (pin "26") (pinfunction "26_26") (pintype "passive"))
    )
    (net (code "297") (name "unconnected-(J12-Pad28)") (class "Default")
      (node (ref "J12") (pin "28") (pinfunction "28_28") (pintype "passive"))
    )
    (net (code "298") (name "unconnected-(J12-Pad30)") (class "Default")
      (node (ref "J12") (pin "30") (pinfunction "30_30") (pintype "passive"))
    )
    (net (code "299") (name "unconnected-(J12-Pad32)") (class "Default")
      (node (ref "J12") (pin "32") (pinfunction "32_32") (pintype "passive"))
    )
    (net (code "300") (name "unconnected-(J12-Pad34)") (class "Default")
      (node (ref "J12") (pin "34") (pinfunction "34_34") (pintype "passive"))
    )
    (net (code "301") (name "unconnected-(J12-Pad36)") (class "Default")
      (node (ref "J12") (pin "36") (pinfunction "36_36") (pintype "passive"))
    )
    (net (code "302") (name "unconnected-(J12-Pad38)") (class "Default")
      (node (ref "J12") (pin "38") (pinfunction "38_38") (pintype "passive"))
    )
    (net (code "303") (name "unconnected-(J12-Pad40)") (class "Default")
      (node (ref "J12") (pin "40") (pinfunction "40_40") (pintype "passive"))
    )
    (net (code "304") (name "unconnected-(J12-Pad42)") (class "Default")
      (node (ref "J12") (pin "42") (pinfunction "42_42") (pintype "passive"))
    )
    (net (code "305") (name "unconnected-(J12-Pad44)") (class "Default")
      (node (ref "J12") (pin "44") (pinfunction "44_44") (pintype "passive"))
    )
    (net (code "306") (name "unconnected-(J12-Pad46)") (class "Default")
      (node (ref "J12") (pin "46") (pinfunction "46_46") (pintype "passive"))
    )
    (net (code "307") (name "unconnected-(J12-Pad48)") (class "Default")
      (node (ref "J12") (pin "48") (pinfunction "48_48") (pintype "passive"))
    )
    (net (code "308") (name "unconnected-(J12-Pad50)") (class "Default")
      (node (ref "J12") (pin "50") (pinfunction "50_50") (pintype "passive"))
    )
  )
)
